# OutputIndicator_v1p2.net
KiCad netlist of a schematic drawn in EAGLE
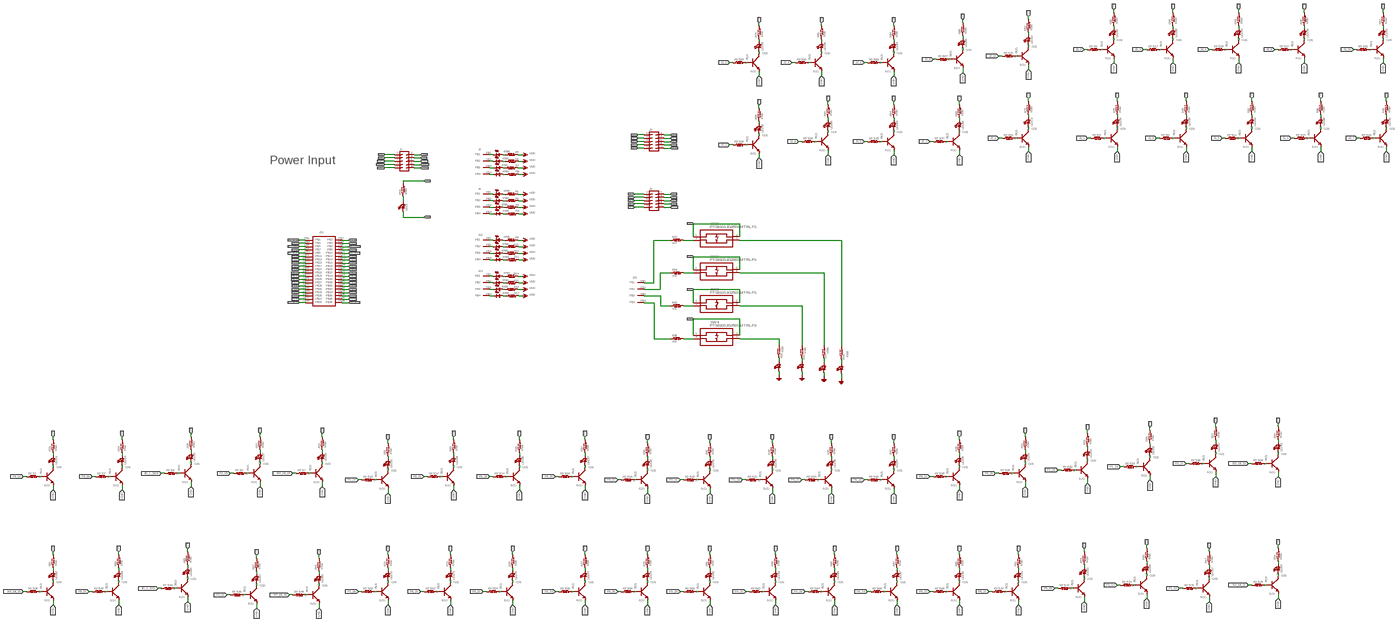
[diagram p0: schematic, sheet 1, overview]
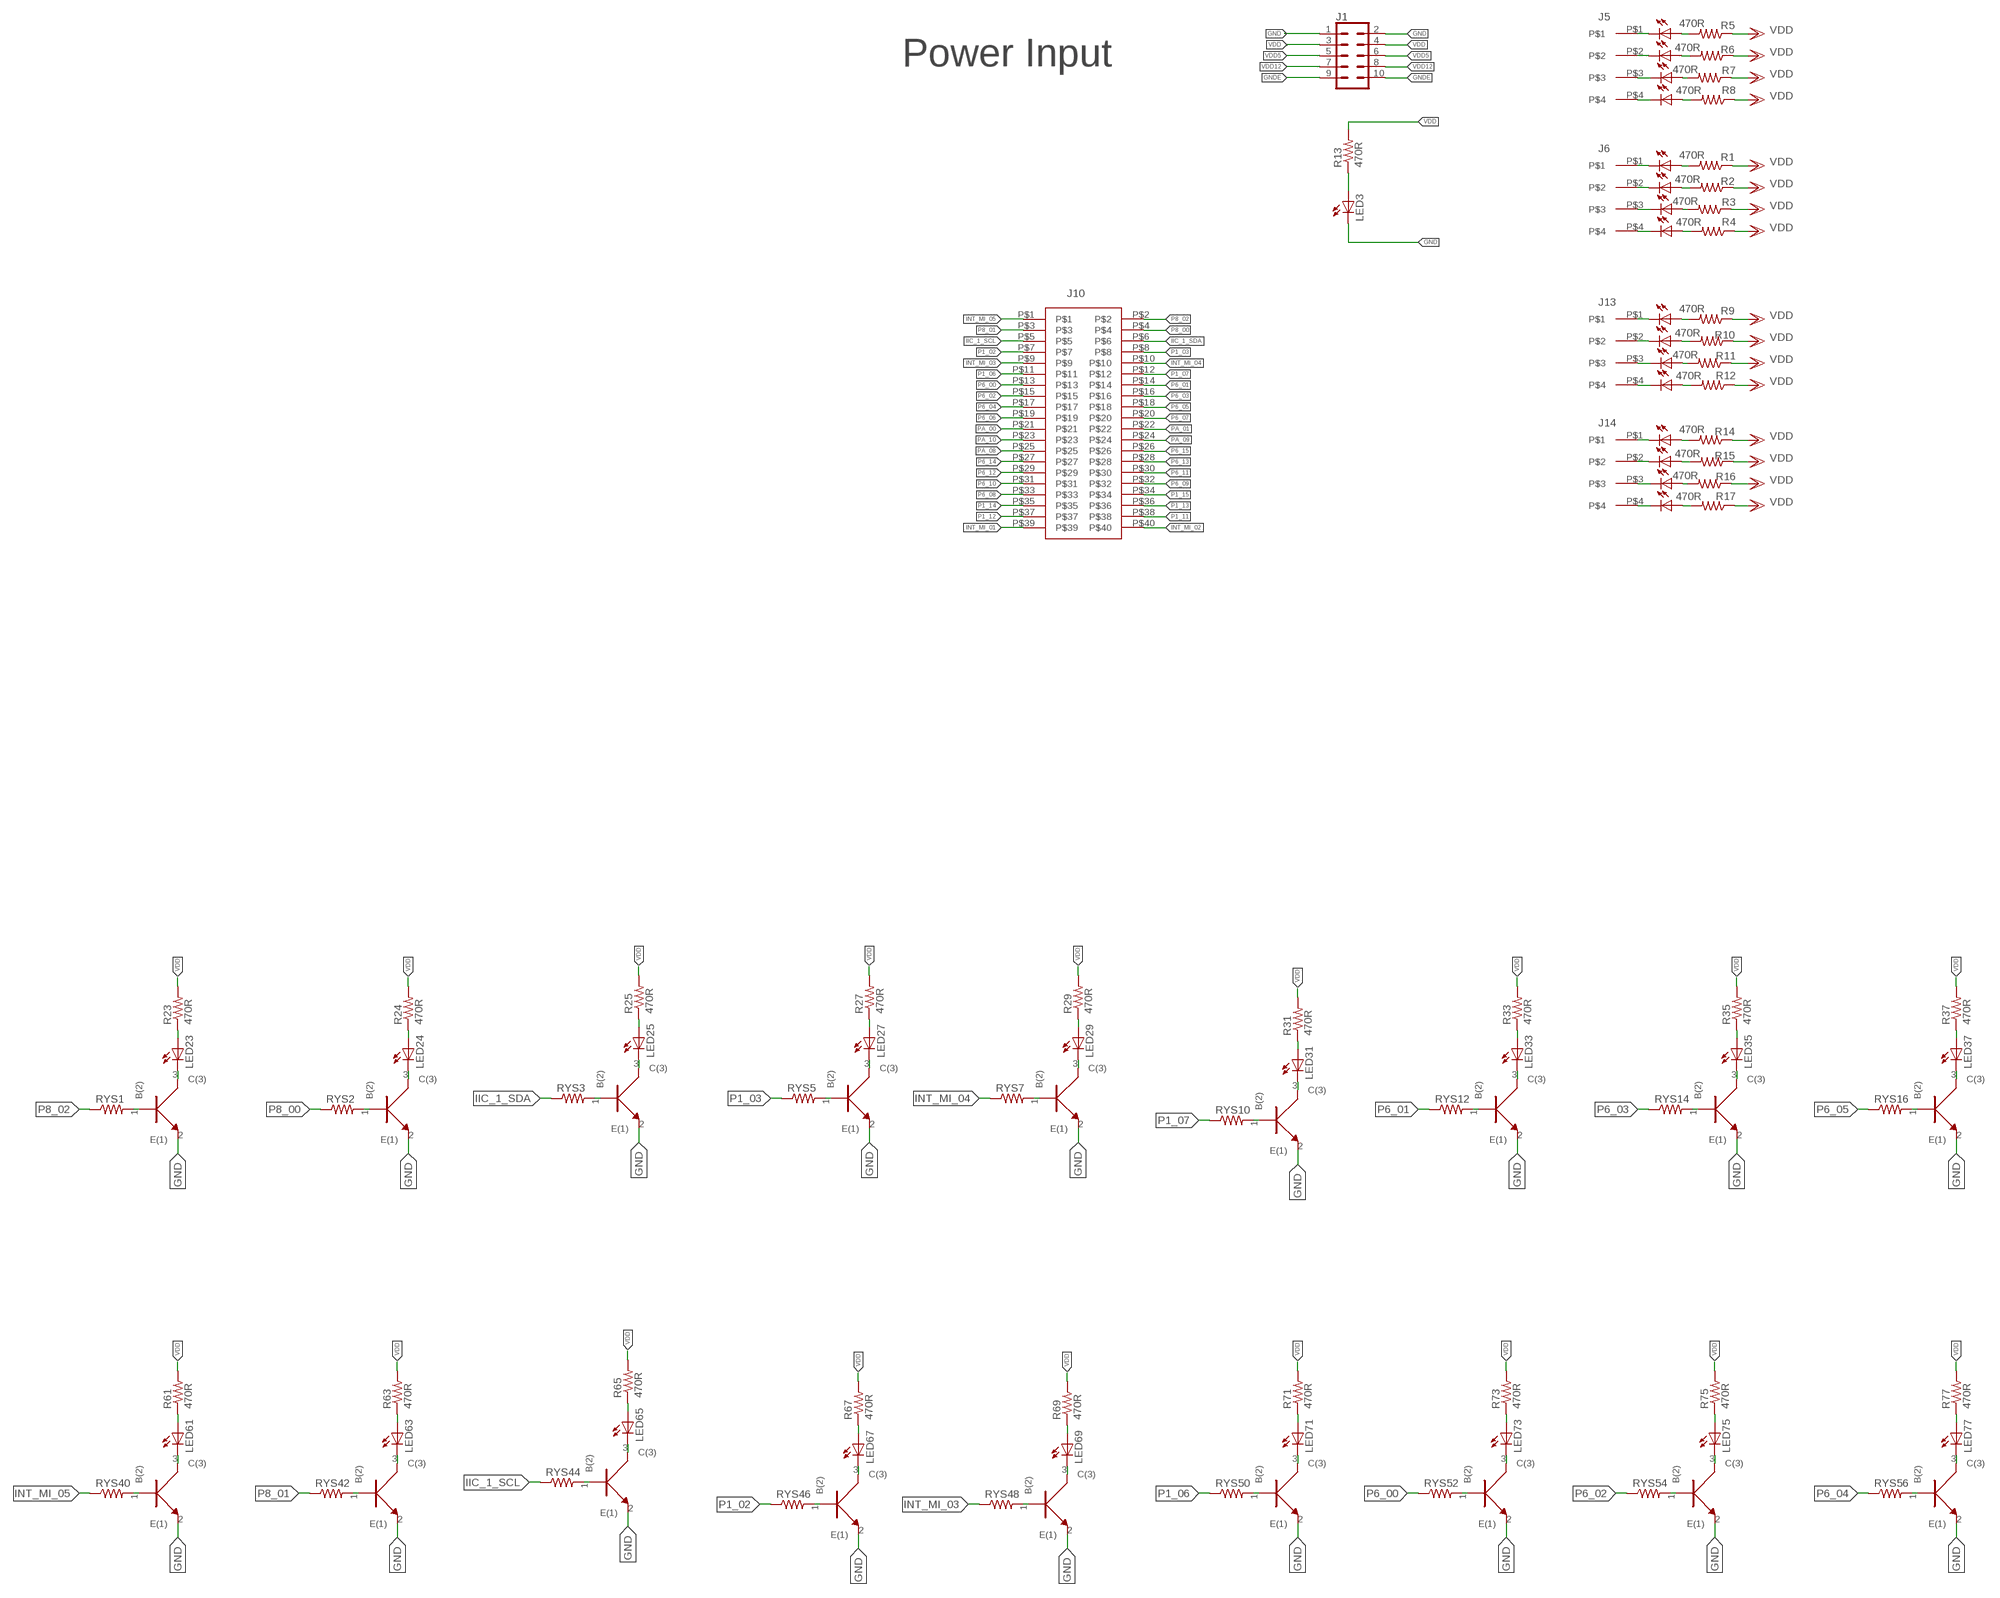
[diagram p1: schematic, sheet 1, part 1 of 5]
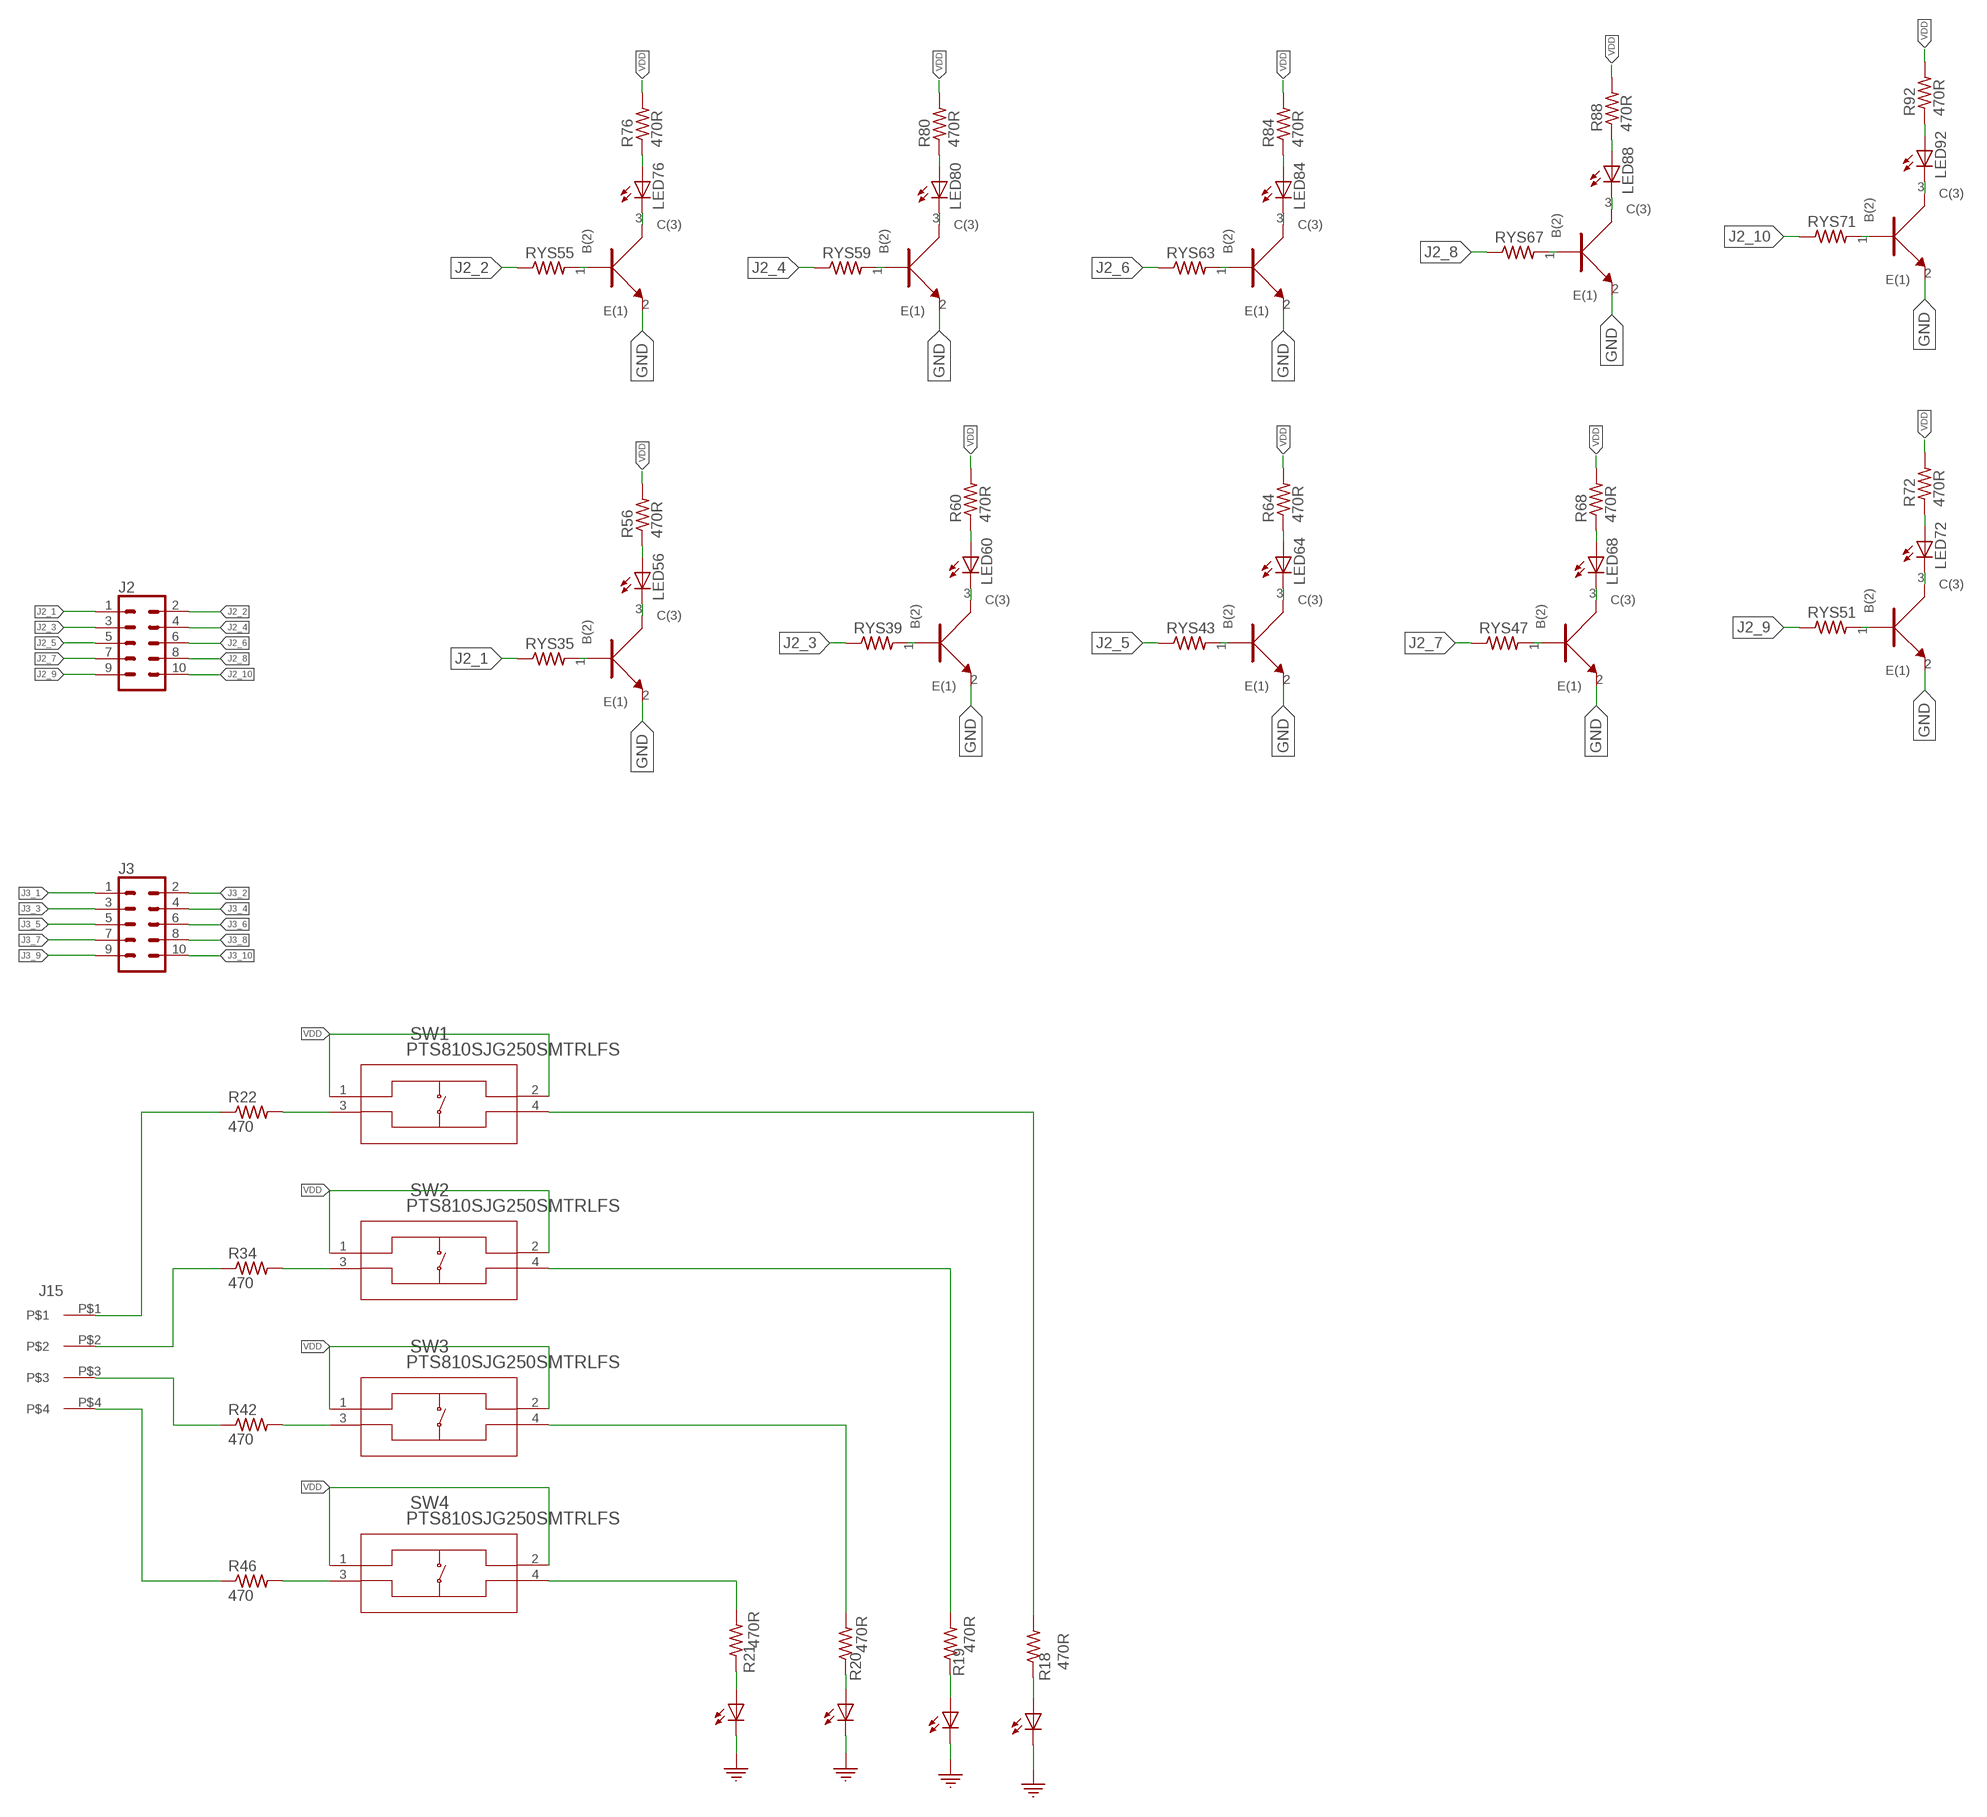
[diagram p2: schematic, sheet 1, part 2 of 5]
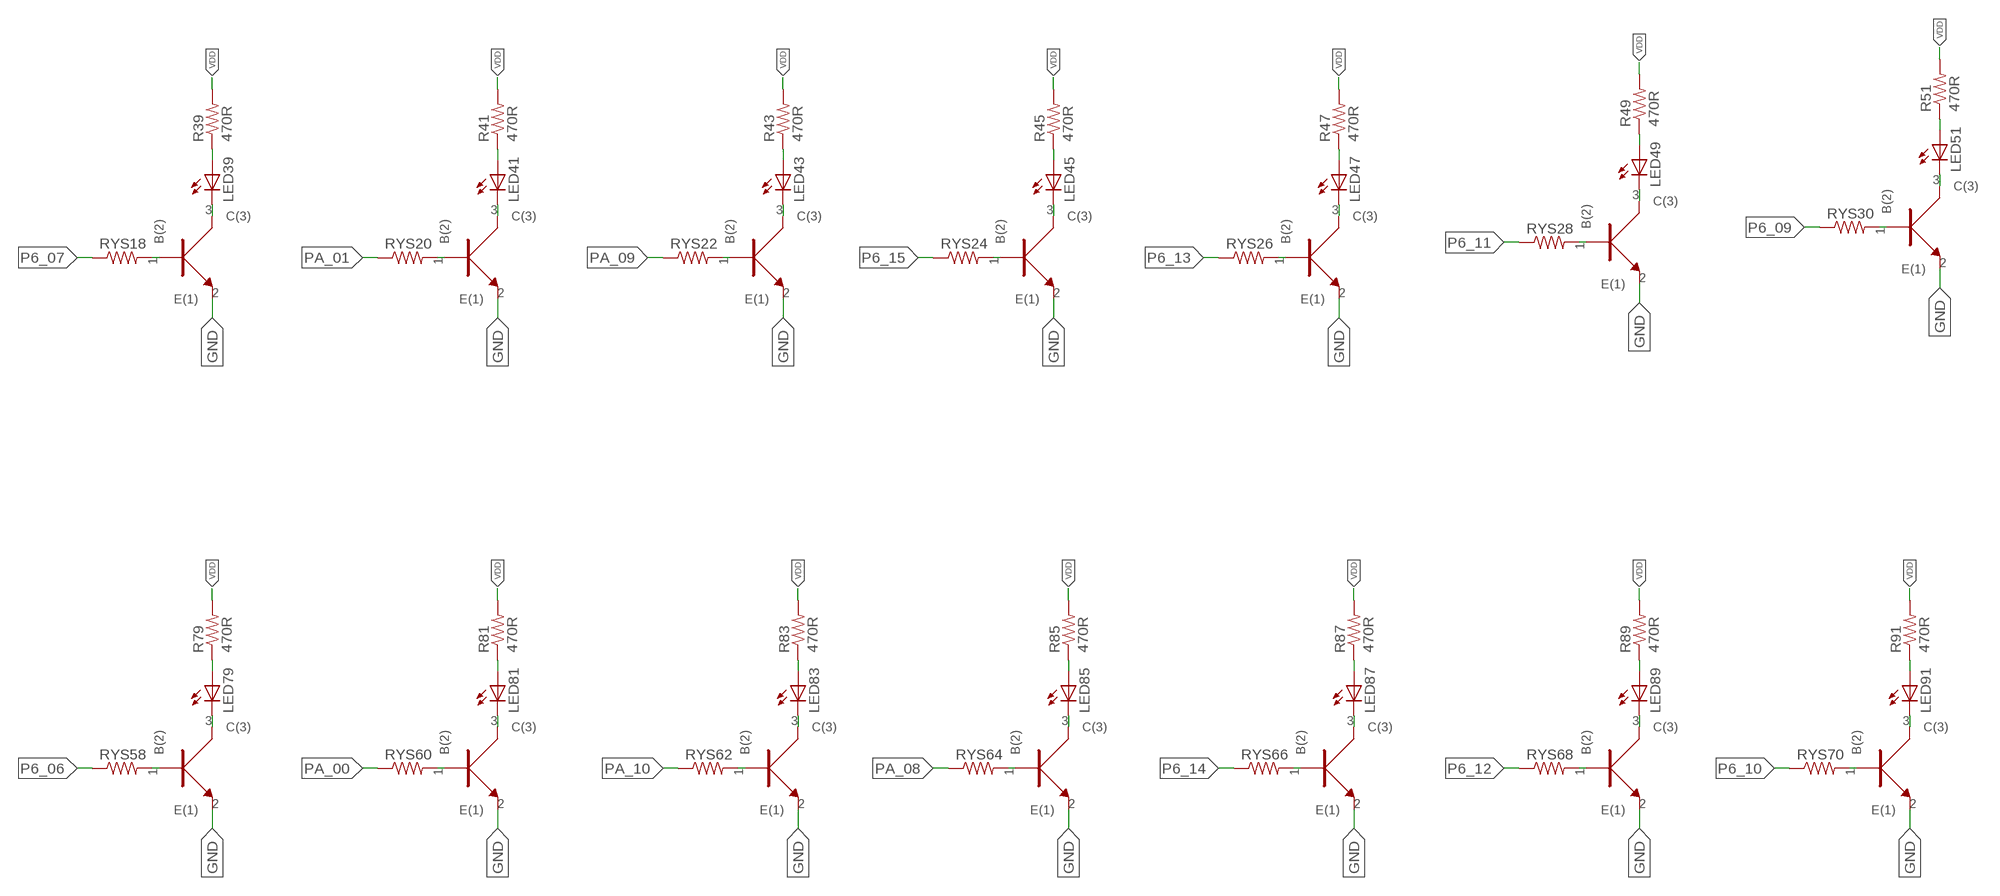
[diagram p3: schematic, sheet 1, part 3 of 5]
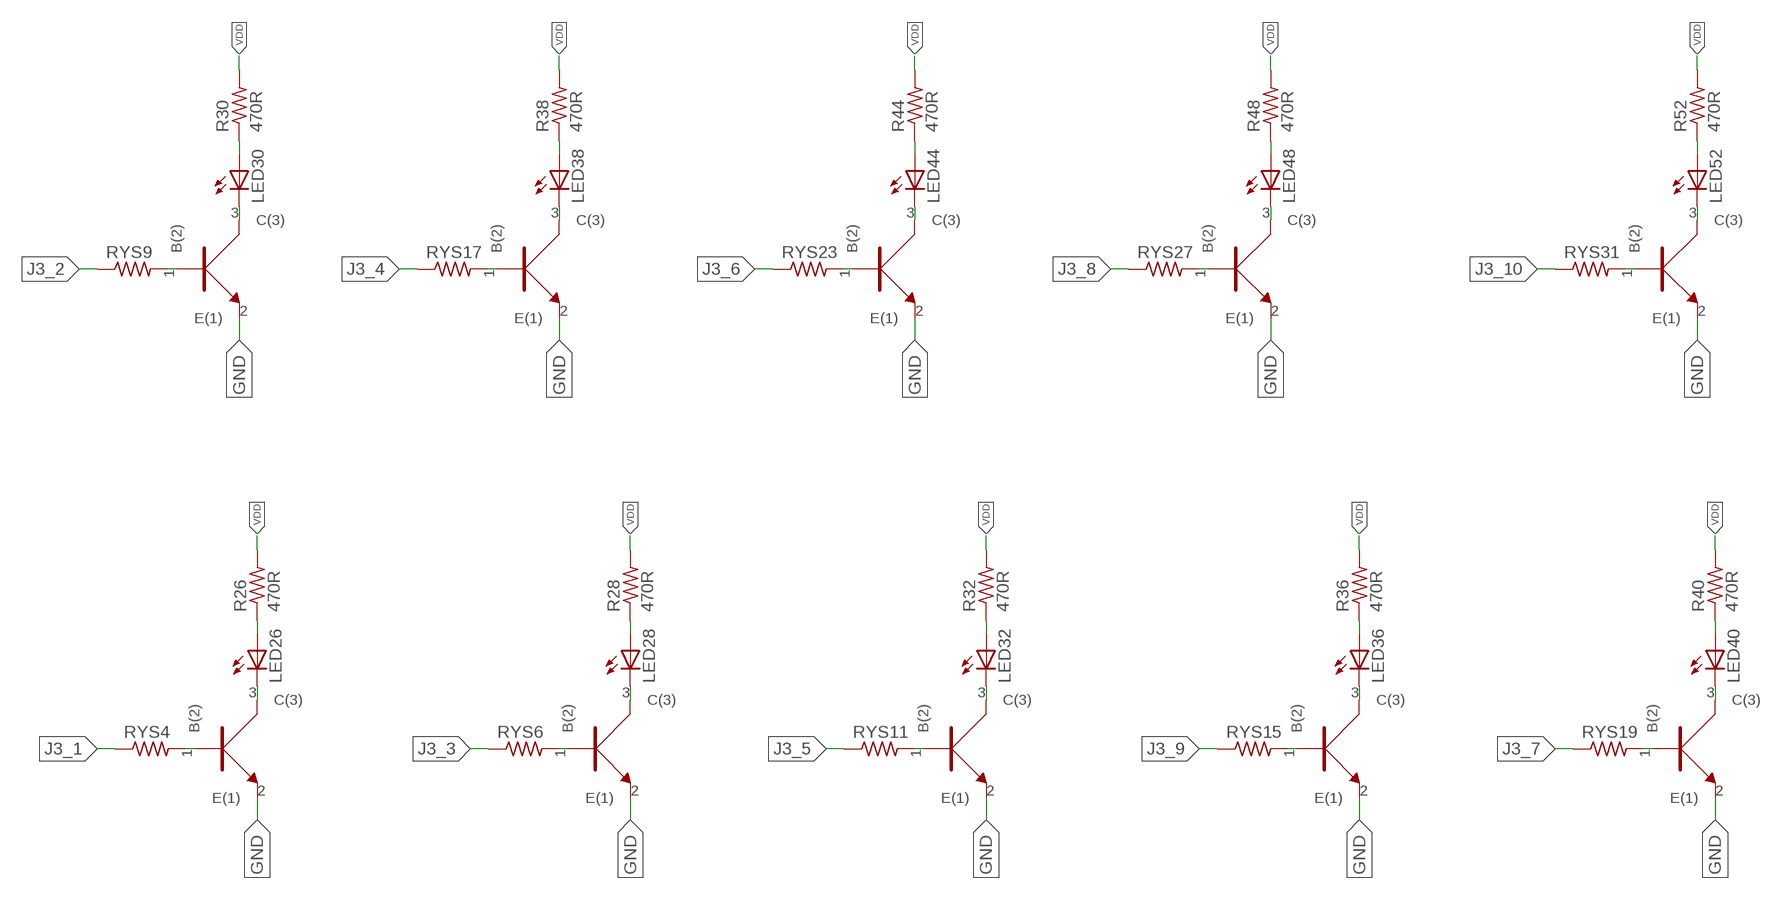
[diagram p4: schematic, sheet 1, part 4 of 5]
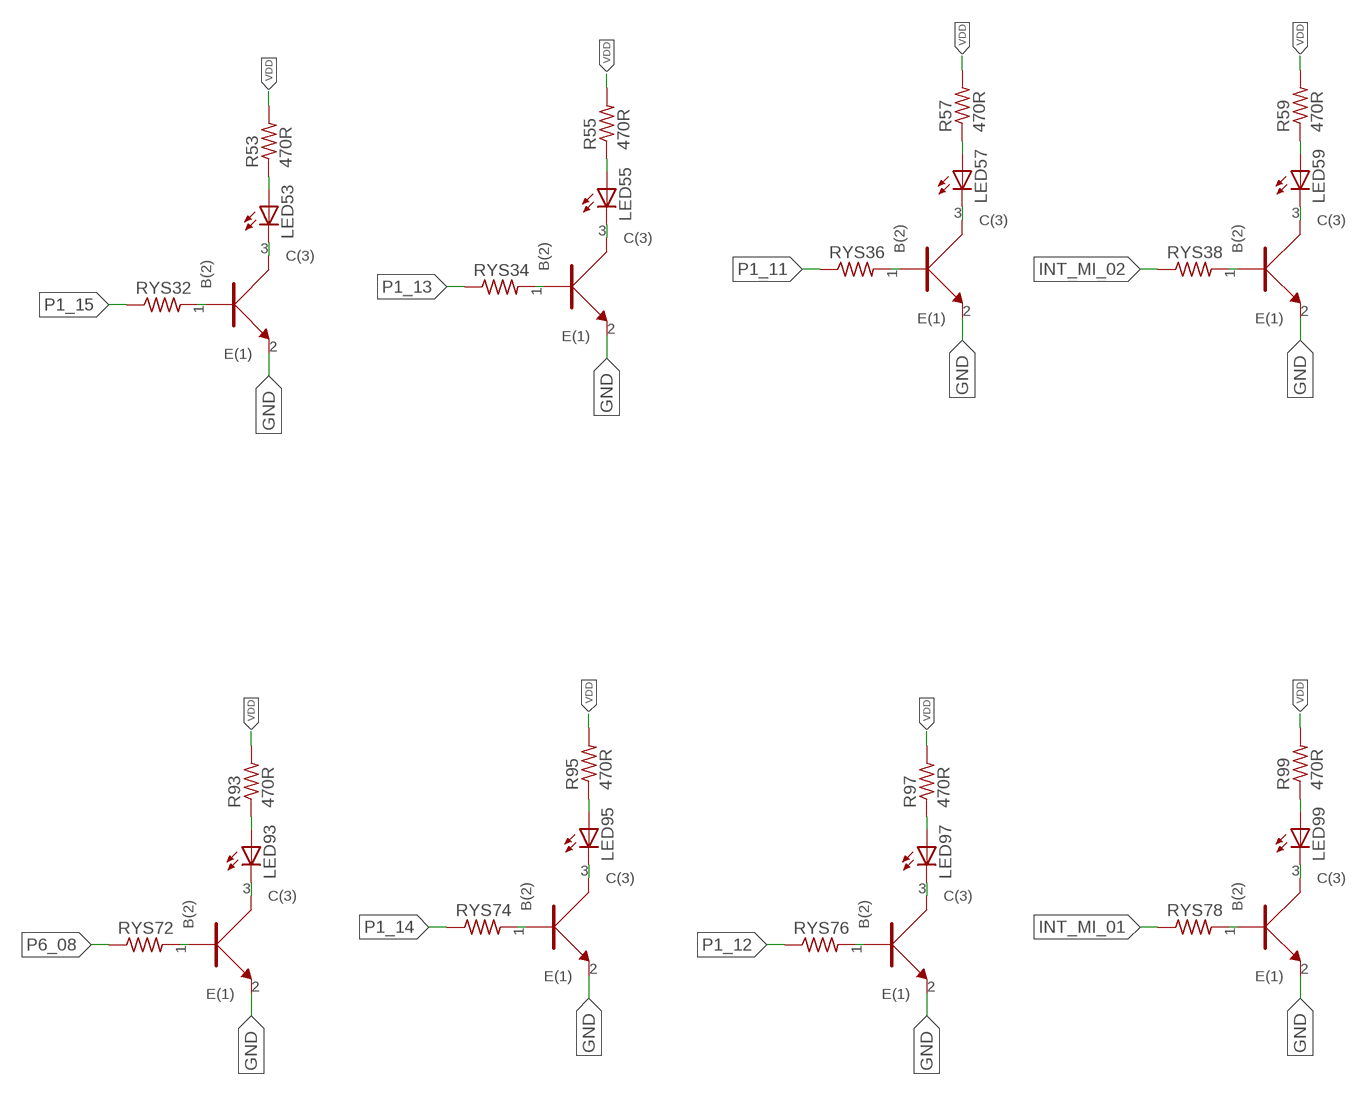
[diagram p5: schematic, sheet 1, part 5 of 5]

(export (version "E")
  (design (tool "Eeschema 10.0.6"))
  (components
    (comp (ref "J1")
      (value "CONN_05X2PTH")
      (footprint "eagle-import:2X5")
      (libsource (lib "eagle-import") (part "CONN_05X2PTH"))
    )
    (comp (ref "J2")
      (value "CONN_05X2PTH")
      (footprint "eagle-import:2X5")
      (libsource (lib "eagle-import") (part "CONN_05X2PTH"))
    )
    (comp (ref "J3")
      (value "CONN_05X2PTH")
      (footprint "eagle-import:2X5")
      (libsource (lib "eagle-import") (part "CONN_05X2PTH"))
    )
    (comp (ref "J5")
      (value "3.81MM_1_X_4_RT_ANGLE_PLUG_HEADER")
      (footprint "eagle-import:1X4_3.81MM_PITCH")
      (libsource (lib "eagle-import") (part "3.81MM_1_X_4_RT_ANGLE_PLUG_HEADER"))
    )
    (comp (ref "J6")
      (value "3.81MM_1_X_4_RT_ANGLE_PLUG_HEADER")
      (footprint "eagle-import:1X4_3.81MM_PITCH")
      (libsource (lib "eagle-import") (part "3.81MM_1_X_4_RT_ANGLE_PLUG_HEADER"))
    )
    (comp (ref "J10")
      (value "HEADER_2_X_20_GENERIC")
      (footprint "eagle-import:HEADER_2_X_20_.1_INCH")
      (libsource (lib "eagle-import") (part "HEADER_2_X_20_GENERIC"))
    )
    (comp (ref "J13")
      (value "3.81MM_1_X_4_RT_ANGLE_PLUG_HEADER")
      (footprint "eagle-import:1X4_3.81MM_PITCH")
      (libsource (lib "eagle-import") (part "3.81MM_1_X_4_RT_ANGLE_PLUG_HEADER"))
    )
    (comp (ref "J14")
      (value "3.81MM_1_X_4_RT_ANGLE_PLUG_HEADER")
      (footprint "eagle-import:1X4_3.81MM_PITCH")
      (libsource (lib "eagle-import") (part "3.81MM_1_X_4_RT_ANGLE_PLUG_HEADER"))
    )
    (comp (ref "J15")
      (value "3.81MM_1_X_4_RT_ANGLE_PLUG_HEADER")
      (footprint "eagle-import:1X4_3.81MM_PITCH")
      (libsource (lib "eagle-import") (part "3.81MM_1_X_4_RT_ANGLE_PLUG_HEADER"))
    )
    (comp (ref "LED1")
      (value "LED_0805_GREEN")
      (footprint "eagle-import:LED_0805_GREEN")
      (libsource (lib "eagle-import") (part "LED_0805_GREEN"))
    )
    (comp (ref "LED2")
      (value "LED_0805_GREEN")
      (footprint "eagle-import:LED_0805_GREEN")
      (libsource (lib "eagle-import") (part "LED_0805_GREEN"))
    )
    (comp (ref "LED3")
      (value "LED_0805_GREEN")
      (footprint "eagle-import:LED_0805_GREEN")
      (libsource (lib "eagle-import") (part "LED_0805_GREEN"))
    )
    (comp (ref "LED4")
      (value "LED_0805_GREEN")
      (footprint "eagle-import:LED_0805_GREEN")
      (libsource (lib "eagle-import") (part "LED_0805_GREEN"))
    )
    (comp (ref "LED5")
      (value "LED_0805_GREEN")
      (footprint "eagle-import:LED_0805_GREEN")
      (libsource (lib "eagle-import") (part "LED_0805_GREEN"))
    )
    (comp (ref "LED6")
      (value "LED_0805_GREEN")
      (footprint "eagle-import:LED_0805_GREEN")
      (libsource (lib "eagle-import") (part "LED_0805_GREEN"))
    )
    (comp (ref "LED7")
      (value "LED_0805_GREEN")
      (footprint "eagle-import:LED_0805_GREEN")
      (libsource (lib "eagle-import") (part "LED_0805_GREEN"))
    )
    (comp (ref "LED8")
      (value "LED_0805_GREEN")
      (footprint "eagle-import:LED_0805_GREEN")
      (libsource (lib "eagle-import") (part "LED_0805_GREEN"))
    )
    (comp (ref "LED9")
      (value "LED_0805_GREEN")
      (footprint "eagle-import:LED_0805_GREEN")
      (libsource (lib "eagle-import") (part "LED_0805_GREEN"))
    )
    (comp (ref "LED10")
      (value "LED_0805_GREEN")
      (footprint "eagle-import:LED_0805_GREEN")
      (libsource (lib "eagle-import") (part "LED_0805_GREEN"))
    )
    (comp (ref "LED11")
      (value "LED_0805_GREEN")
      (footprint "eagle-import:LED_0805_GREEN")
      (libsource (lib "eagle-import") (part "LED_0805_GREEN"))
    )
    (comp (ref "LED12")
      (value "LED_0805_GREEN")
      (footprint "eagle-import:LED_0805_GREEN")
      (libsource (lib "eagle-import") (part "LED_0805_GREEN"))
    )
    (comp (ref "LED13")
      (value "LED_0805_GREEN")
      (footprint "eagle-import:LED_0805_GREEN")
      (libsource (lib "eagle-import") (part "LED_0805_GREEN"))
    )
    (comp (ref "LED14")
      (value "LED_0805_GREEN")
      (footprint "eagle-import:LED_0805_GREEN")
      (libsource (lib "eagle-import") (part "LED_0805_GREEN"))
    )
    (comp (ref "LED15")
      (value "LED_0805_GREEN")
      (footprint "eagle-import:LED_0805_GREEN")
      (libsource (lib "eagle-import") (part "LED_0805_GREEN"))
    )
    (comp (ref "LED16")
      (value "LED_0805_GREEN")
      (footprint "eagle-import:LED_0805_GREEN")
      (libsource (lib "eagle-import") (part "LED_0805_GREEN"))
    )
    (comp (ref "LED17")
      (value "LED_0805_GREEN")
      (footprint "eagle-import:LED_0805_GREEN")
      (libsource (lib "eagle-import") (part "LED_0805_GREEN"))
    )
    (comp (ref "LED18")
      (value "LED_0805_GREEN")
      (footprint "eagle-import:LED_0805_GREEN")
      (libsource (lib "eagle-import") (part "LED_0805_GREEN"))
    )
    (comp (ref "LED19")
      (value "LED_0805_GREEN")
      (footprint "eagle-import:LED_0805_GREEN")
      (libsource (lib "eagle-import") (part "LED_0805_GREEN"))
    )
    (comp (ref "LED20")
      (value "LED_0805_GREEN")
      (footprint "eagle-import:LED_0805_GREEN")
      (libsource (lib "eagle-import") (part "LED_0805_GREEN"))
    )
    (comp (ref "LED21")
      (value "LED_0805_GREEN")
      (footprint "eagle-import:LED_0805_GREEN")
      (libsource (lib "eagle-import") (part "LED_0805_GREEN"))
    )
    (comp (ref "LED23")
      (value "LED_0805_GREEN")
      (footprint "eagle-import:LED_0805_GREEN")
      (libsource (lib "eagle-import") (part "LED_0805_GREEN"))
    )
    (comp (ref "LED24")
      (value "LED_0805_GREEN")
      (footprint "eagle-import:LED_0805_GREEN")
      (libsource (lib "eagle-import") (part "LED_0805_GREEN"))
    )
    (comp (ref "LED25")
      (value "LED_0805_GREEN")
      (footprint "eagle-import:LED_0805_GREEN")
      (libsource (lib "eagle-import") (part "LED_0805_GREEN"))
    )
    (comp (ref "LED26")
      (value "LED_0805_GREEN")
      (footprint "eagle-import:LED_0805_GREEN")
      (libsource (lib "eagle-import") (part "LED_0805_GREEN"))
    )
    (comp (ref "LED27")
      (value "LED_0805_GREEN")
      (footprint "eagle-import:LED_0805_GREEN")
      (libsource (lib "eagle-import") (part "LED_0805_GREEN"))
    )
    (comp (ref "LED28")
      (value "LED_0805_GREEN")
      (footprint "eagle-import:LED_0805_GREEN")
      (libsource (lib "eagle-import") (part "LED_0805_GREEN"))
    )
    (comp (ref "LED29")
      (value "LED_0805_GREEN")
      (footprint "eagle-import:LED_0805_GREEN")
      (libsource (lib "eagle-import") (part "LED_0805_GREEN"))
    )
    (comp (ref "LED30")
      (value "LED_0805_GREEN")
      (footprint "eagle-import:LED_0805_GREEN")
      (libsource (lib "eagle-import") (part "LED_0805_GREEN"))
    )
    (comp (ref "LED31")
      (value "LED_0805_GREEN")
      (footprint "eagle-import:LED_0805_GREEN")
      (libsource (lib "eagle-import") (part "LED_0805_GREEN"))
    )
    (comp (ref "LED32")
      (value "LED_0805_GREEN")
      (footprint "eagle-import:LED_0805_GREEN")
      (libsource (lib "eagle-import") (part "LED_0805_GREEN"))
    )
    (comp (ref "LED33")
      (value "LED_0805_GREEN")
      (footprint "eagle-import:LED_0805_GREEN")
      (libsource (lib "eagle-import") (part "LED_0805_GREEN"))
    )
    (comp (ref "LED35")
      (value "LED_0805_GREEN")
      (footprint "eagle-import:LED_0805_GREEN")
      (libsource (lib "eagle-import") (part "LED_0805_GREEN"))
    )
    (comp (ref "LED36")
      (value "LED_0805_GREEN")
      (footprint "eagle-import:LED_0805_GREEN")
      (libsource (lib "eagle-import") (part "LED_0805_GREEN"))
    )
    (comp (ref "LED37")
      (value "LED_0805_GREEN")
      (footprint "eagle-import:LED_0805_GREEN")
      (libsource (lib "eagle-import") (part "LED_0805_GREEN"))
    )
    (comp (ref "LED38")
      (value "LED_0805_GREEN")
      (footprint "eagle-import:LED_0805_GREEN")
      (libsource (lib "eagle-import") (part "LED_0805_GREEN"))
    )
    (comp (ref "LED39")
      (value "LED_0805_GREEN")
      (footprint "eagle-import:LED_0805_GREEN")
      (libsource (lib "eagle-import") (part "LED_0805_GREEN"))
    )
    (comp (ref "LED40")
      (value "LED_0805_GREEN")
      (footprint "eagle-import:LED_0805_GREEN")
      (libsource (lib "eagle-import") (part "LED_0805_GREEN"))
    )
    (comp (ref "LED41")
      (value "LED_0805_GREEN")
      (footprint "eagle-import:LED_0805_GREEN")
      (libsource (lib "eagle-import") (part "LED_0805_GREEN"))
    )
    (comp (ref "LED43")
      (value "LED_0805_GREEN")
      (footprint "eagle-import:LED_0805_GREEN")
      (libsource (lib "eagle-import") (part "LED_0805_GREEN"))
    )
    (comp (ref "LED44")
      (value "LED_0805_GREEN")
      (footprint "eagle-import:LED_0805_GREEN")
      (libsource (lib "eagle-import") (part "LED_0805_GREEN"))
    )
    (comp (ref "LED45")
      (value "LED_0805_GREEN")
      (footprint "eagle-import:LED_0805_GREEN")
      (libsource (lib "eagle-import") (part "LED_0805_GREEN"))
    )
    (comp (ref "LED47")
      (value "LED_0805_GREEN")
      (footprint "eagle-import:LED_0805_GREEN")
      (libsource (lib "eagle-import") (part "LED_0805_GREEN"))
    )
    (comp (ref "LED48")
      (value "LED_0805_GREEN")
      (footprint "eagle-import:LED_0805_GREEN")
      (libsource (lib "eagle-import") (part "LED_0805_GREEN"))
    )
    (comp (ref "LED49")
      (value "LED_0805_GREEN")
      (footprint "eagle-import:LED_0805_GREEN")
      (libsource (lib "eagle-import") (part "LED_0805_GREEN"))
    )
    (comp (ref "LED51")
      (value "LED_0805_GREEN")
      (footprint "eagle-import:LED_0805_GREEN")
      (libsource (lib "eagle-import") (part "LED_0805_GREEN"))
    )
    (comp (ref "LED52")
      (value "LED_0805_GREEN")
      (footprint "eagle-import:LED_0805_GREEN")
      (libsource (lib "eagle-import") (part "LED_0805_GREEN"))
    )
    (comp (ref "LED53")
      (value "LED_0805_GREEN")
      (footprint "eagle-import:LED_0805_GREEN")
      (libsource (lib "eagle-import") (part "LED_0805_GREEN"))
    )
    (comp (ref "LED55")
      (value "LED_0805_GREEN")
      (footprint "eagle-import:LED_0805_GREEN")
      (libsource (lib "eagle-import") (part "LED_0805_GREEN"))
    )
    (comp (ref "LED56")
      (value "LED_0805_GREEN")
      (footprint "eagle-import:LED_0805_GREEN")
      (libsource (lib "eagle-import") (part "LED_0805_GREEN"))
    )
    (comp (ref "LED57")
      (value "LED_0805_GREEN")
      (footprint "eagle-import:LED_0805_GREEN")
      (libsource (lib "eagle-import") (part "LED_0805_GREEN"))
    )
    (comp (ref "LED59")
      (value "LED_0805_GREEN")
      (footprint "eagle-import:LED_0805_GREEN")
      (libsource (lib "eagle-import") (part "LED_0805_GREEN"))
    )
    (comp (ref "LED60")
      (value "LED_0805_GREEN")
      (footprint "eagle-import:LED_0805_GREEN")
      (libsource (lib "eagle-import") (part "LED_0805_GREEN"))
    )
    (comp (ref "LED61")
      (value "LED_0805_GREEN")
      (footprint "eagle-import:LED_0805_GREEN")
      (libsource (lib "eagle-import") (part "LED_0805_GREEN"))
    )
    (comp (ref "LED63")
      (value "LED_0805_GREEN")
      (footprint "eagle-import:LED_0805_GREEN")
      (libsource (lib "eagle-import") (part "LED_0805_GREEN"))
    )
    (comp (ref "LED64")
      (value "LED_0805_GREEN")
      (footprint "eagle-import:LED_0805_GREEN")
      (libsource (lib "eagle-import") (part "LED_0805_GREEN"))
    )
    (comp (ref "LED65")
      (value "LED_0805_GREEN")
      (footprint "eagle-import:LED_0805_GREEN")
      (libsource (lib "eagle-import") (part "LED_0805_GREEN"))
    )
    (comp (ref "LED67")
      (value "LED_0805_GREEN")
      (footprint "eagle-import:LED_0805_GREEN")
      (libsource (lib "eagle-import") (part "LED_0805_GREEN"))
    )
    (comp (ref "LED68")
      (value "LED_0805_GREEN")
      (footprint "eagle-import:LED_0805_GREEN")
      (libsource (lib "eagle-import") (part "LED_0805_GREEN"))
    )
    (comp (ref "LED69")
      (value "LED_0805_GREEN")
      (footprint "eagle-import:LED_0805_GREEN")
      (libsource (lib "eagle-import") (part "LED_0805_GREEN"))
    )
    (comp (ref "LED71")
      (value "LED_0805_GREEN")
      (footprint "eagle-import:LED_0805_GREEN")
      (libsource (lib "eagle-import") (part "LED_0805_GREEN"))
    )
    (comp (ref "LED72")
      (value "LED_0805_GREEN")
      (footprint "eagle-import:LED_0805_GREEN")
      (libsource (lib "eagle-import") (part "LED_0805_GREEN"))
    )
    (comp (ref "LED73")
      (value "LED_0805_GREEN")
      (footprint "eagle-import:LED_0805_GREEN")
      (libsource (lib "eagle-import") (part "LED_0805_GREEN"))
    )
    (comp (ref "LED75")
      (value "LED_0805_GREEN")
      (footprint "eagle-import:LED_0805_GREEN")
      (libsource (lib "eagle-import") (part "LED_0805_GREEN"))
    )
    (comp (ref "LED76")
      (value "LED_0805_GREEN")
      (footprint "eagle-import:LED_0805_GREEN")
      (libsource (lib "eagle-import") (part "LED_0805_GREEN"))
    )
    (comp (ref "LED77")
      (value "LED_0805_GREEN")
      (footprint "eagle-import:LED_0805_GREEN")
      (libsource (lib "eagle-import") (part "LED_0805_GREEN"))
    )
    (comp (ref "LED79")
      (value "LED_0805_GREEN")
      (footprint "eagle-import:LED_0805_GREEN")
      (libsource (lib "eagle-import") (part "LED_0805_GREEN"))
    )
    (comp (ref "LED80")
      (value "LED_0805_GREEN")
      (footprint "eagle-import:LED_0805_GREEN")
      (libsource (lib "eagle-import") (part "LED_0805_GREEN"))
    )
    (comp (ref "LED81")
      (value "LED_0805_GREEN")
      (footprint "eagle-import:LED_0805_GREEN")
      (libsource (lib "eagle-import") (part "LED_0805_GREEN"))
    )
    (comp (ref "LED83")
      (value "LED_0805_GREEN")
      (footprint "eagle-import:LED_0805_GREEN")
      (libsource (lib "eagle-import") (part "LED_0805_GREEN"))
    )
    (comp (ref "LED84")
      (value "LED_0805_GREEN")
      (footprint "eagle-import:LED_0805_GREEN")
      (libsource (lib "eagle-import") (part "LED_0805_GREEN"))
    )
    (comp (ref "LED85")
      (value "LED_0805_GREEN")
      (footprint "eagle-import:LED_0805_GREEN")
      (libsource (lib "eagle-import") (part "LED_0805_GREEN"))
    )
    (comp (ref "LED87")
      (value "LED_0805_GREEN")
      (footprint "eagle-import:LED_0805_GREEN")
      (libsource (lib "eagle-import") (part "LED_0805_GREEN"))
    )
    (comp (ref "LED88")
      (value "LED_0805_GREEN")
      (footprint "eagle-import:LED_0805_GREEN")
      (libsource (lib "eagle-import") (part "LED_0805_GREEN"))
    )
    (comp (ref "LED89")
      (value "LED_0805_GREEN")
      (footprint "eagle-import:LED_0805_GREEN")
      (libsource (lib "eagle-import") (part "LED_0805_GREEN"))
    )
    (comp (ref "LED91")
      (value "LED_0805_GREEN")
      (footprint "eagle-import:LED_0805_GREEN")
      (libsource (lib "eagle-import") (part "LED_0805_GREEN"))
    )
    (comp (ref "LED92")
      (value "LED_0805_GREEN")
      (footprint "eagle-import:LED_0805_GREEN")
      (libsource (lib "eagle-import") (part "LED_0805_GREEN"))
    )
    (comp (ref "LED93")
      (value "LED_0805_GREEN")
      (footprint "eagle-import:LED_0805_GREEN")
      (libsource (lib "eagle-import") (part "LED_0805_GREEN"))
    )
    (comp (ref "LED95")
      (value "LED_0805_GREEN")
      (footprint "eagle-import:LED_0805_GREEN")
      (libsource (lib "eagle-import") (part "LED_0805_GREEN"))
    )
    (comp (ref "LED97")
      (value "LED_0805_GREEN")
      (footprint "eagle-import:LED_0805_GREEN")
      (libsource (lib "eagle-import") (part "LED_0805_GREEN"))
    )
    (comp (ref "LED99")
      (value "LED_0805_GREEN")
      (footprint "eagle-import:LED_0805_GREEN")
      (libsource (lib "eagle-import") (part "LED_0805_GREEN"))
    )
    (comp (ref "R1")
      (value "470R")
      (footprint "eagle-import:0402")
      (libsource (lib "eagle-import") (part "R_0402"))
    )
    (comp (ref "R2")
      (value "470R")
      (footprint "eagle-import:0402")
      (libsource (lib "eagle-import") (part "R_0402"))
    )
    (comp (ref "R3")
      (value "470R")
      (footprint "eagle-import:0402")
      (libsource (lib "eagle-import") (part "R_0402"))
    )
    (comp (ref "R4")
      (value "470R")
      (footprint "eagle-import:0402")
      (libsource (lib "eagle-import") (part "R_0402"))
    )
    (comp (ref "R5")
      (value "470R")
      (footprint "eagle-import:0402")
      (libsource (lib "eagle-import") (part "R_0402"))
    )
    (comp (ref "R6")
      (value "470R")
      (footprint "eagle-import:0402")
      (libsource (lib "eagle-import") (part "R_0402"))
    )
    (comp (ref "R7")
      (value "470R")
      (footprint "eagle-import:0402")
      (libsource (lib "eagle-import") (part "R_0402"))
    )
    (comp (ref "R8")
      (value "470R")
      (footprint "eagle-import:0402")
      (libsource (lib "eagle-import") (part "R_0402"))
    )
    (comp (ref "R9")
      (value "470R")
      (footprint "eagle-import:0402")
      (libsource (lib "eagle-import") (part "R_0402"))
    )
    (comp (ref "R10")
      (value "470R")
      (footprint "eagle-import:0402")
      (libsource (lib "eagle-import") (part "R_0402"))
    )
    (comp (ref "R11")
      (value "470R")
      (footprint "eagle-import:0402")
      (libsource (lib "eagle-import") (part "R_0402"))
    )
    (comp (ref "R12")
      (value "470R")
      (footprint "eagle-import:0402")
      (libsource (lib "eagle-import") (part "R_0402"))
    )
    (comp (ref "R13")
      (value "470R")
      (footprint "eagle-import:0402")
      (libsource (lib "eagle-import") (part "R_0402"))
    )
    (comp (ref "R14")
      (value "470R")
      (footprint "eagle-import:0402")
      (libsource (lib "eagle-import") (part "R_0402"))
    )
    (comp (ref "R15")
      (value "470R")
      (footprint "eagle-import:0402")
      (libsource (lib "eagle-import") (part "R_0402"))
    )
    (comp (ref "R16")
      (value "470R")
      (footprint "eagle-import:0402")
      (libsource (lib "eagle-import") (part "R_0402"))
    )
    (comp (ref "R17")
      (value "470R")
      (footprint "eagle-import:0402")
      (libsource (lib "eagle-import") (part "R_0402"))
    )
    (comp (ref "R18")
      (value "470R")
      (footprint "eagle-import:0402")
      (libsource (lib "eagle-import") (part "R_0402"))
    )
    (comp (ref "R19")
      (value "470R")
      (footprint "eagle-import:0402")
      (libsource (lib "eagle-import") (part "R_0402"))
    )
    (comp (ref "R20")
      (value "470R")
      (footprint "eagle-import:0402")
      (libsource (lib "eagle-import") (part "R_0402"))
    )
    (comp (ref "R21")
      (value "470R")
      (footprint "eagle-import:0402")
      (libsource (lib "eagle-import") (part "R_0402"))
    )
    (comp (ref "R22")
      (value "470")
      (footprint "eagle-import:0402")
      (libsource (lib "eagle-import") (part "R_0402"))
    )
    (comp (ref "R23")
      (value "470R")
      (footprint "eagle-import:0402")
      (libsource (lib "eagle-import") (part "R_0402"))
    )
    (comp (ref "R24")
      (value "470R")
      (footprint "eagle-import:0402")
      (libsource (lib "eagle-import") (part "R_0402"))
    )
    (comp (ref "R25")
      (value "470R")
      (footprint "eagle-import:0402")
      (libsource (lib "eagle-import") (part "R_0402"))
    )
    (comp (ref "R26")
      (value "470R")
      (footprint "eagle-import:0402")
      (libsource (lib "eagle-import") (part "R_0402"))
    )
    (comp (ref "R27")
      (value "470R")
      (footprint "eagle-import:0402")
      (libsource (lib "eagle-import") (part "R_0402"))
    )
    (comp (ref "R28")
      (value "470R")
      (footprint "eagle-import:0402")
      (libsource (lib "eagle-import") (part "R_0402"))
    )
    (comp (ref "R29")
      (value "470R")
      (footprint "eagle-import:0402")
      (libsource (lib "eagle-import") (part "R_0402"))
    )
    (comp (ref "R30")
      (value "470R")
      (footprint "eagle-import:0402")
      (libsource (lib "eagle-import") (part "R_0402"))
    )
    (comp (ref "R31")
      (value "470R")
      (footprint "eagle-import:0402")
      (libsource (lib "eagle-import") (part "R_0402"))
    )
    (comp (ref "R32")
      (value "470R")
      (footprint "eagle-import:0402")
      (libsource (lib "eagle-import") (part "R_0402"))
    )
    (comp (ref "R33")
      (value "470R")
      (footprint "eagle-import:0402")
      (libsource (lib "eagle-import") (part "R_0402"))
    )
    (comp (ref "R34")
      (value "470")
      (footprint "eagle-import:0402")
      (libsource (lib "eagle-import") (part "R_0402"))
    )
    (comp (ref "R35")
      (value "470R")
      (footprint "eagle-import:0402")
      (libsource (lib "eagle-import") (part "R_0402"))
    )
    (comp (ref "R36")
      (value "470R")
      (footprint "eagle-import:0402")
      (libsource (lib "eagle-import") (part "R_0402"))
    )
    (comp (ref "R37")
      (value "470R")
      (footprint "eagle-import:0402")
      (libsource (lib "eagle-import") (part "R_0402"))
    )
    (comp (ref "R38")
      (value "470R")
      (footprint "eagle-import:0402")
      (libsource (lib "eagle-import") (part "R_0402"))
    )
    (comp (ref "R39")
      (value "470R")
      (footprint "eagle-import:0402")
      (libsource (lib "eagle-import") (part "R_0402"))
    )
    (comp (ref "R40")
      (value "470R")
      (footprint "eagle-import:0402")
      (libsource (lib "eagle-import") (part "R_0402"))
    )
    (comp (ref "R41")
      (value "470R")
      (footprint "eagle-import:0402")
      (libsource (lib "eagle-import") (part "R_0402"))
    )
    (comp (ref "R42")
      (value "470")
      (footprint "eagle-import:0402")
      (libsource (lib "eagle-import") (part "R_0402"))
    )
    (comp (ref "R43")
      (value "470R")
      (footprint "eagle-import:0402")
      (libsource (lib "eagle-import") (part "R_0402"))
    )
    (comp (ref "R44")
      (value "470R")
      (footprint "eagle-import:0402")
      (libsource (lib "eagle-import") (part "R_0402"))
    )
    (comp (ref "R45")
      (value "470R")
      (footprint "eagle-import:0402")
      (libsource (lib "eagle-import") (part "R_0402"))
    )
    (comp (ref "R46")
      (value "470")
      (footprint "eagle-import:0402")
      (libsource (lib "eagle-import") (part "R_0402"))
    )
    (comp (ref "R47")
      (value "470R")
      (footprint "eagle-import:0402")
      (libsource (lib "eagle-import") (part "R_0402"))
    )
    (comp (ref "R48")
      (value "470R")
      (footprint "eagle-import:0402")
      (libsource (lib "eagle-import") (part "R_0402"))
    )
    (comp (ref "R49")
      (value "470R")
      (footprint "eagle-import:0402")
      (libsource (lib "eagle-import") (part "R_0402"))
    )
    (comp (ref "R51")
      (value "470R")
      (footprint "eagle-import:0402")
      (libsource (lib "eagle-import") (part "R_0402"))
    )
    (comp (ref "R52")
      (value "470R")
      (footprint "eagle-import:0402")
      (libsource (lib "eagle-import") (part "R_0402"))
    )
    (comp (ref "R53")
      (value "470R")
      (footprint "eagle-import:0402")
      (libsource (lib "eagle-import") (part "R_0402"))
    )
    (comp (ref "R55")
      (value "470R")
      (footprint "eagle-import:0402")
      (libsource (lib "eagle-import") (part "R_0402"))
    )
    (comp (ref "R56")
      (value "470R")
      (footprint "eagle-import:0402")
      (libsource (lib "eagle-import") (part "R_0402"))
    )
    (comp (ref "R57")
      (value "470R")
      (footprint "eagle-import:0402")
      (libsource (lib "eagle-import") (part "R_0402"))
    )
    (comp (ref "R59")
      (value "470R")
      (footprint "eagle-import:0402")
      (libsource (lib "eagle-import") (part "R_0402"))
    )
    (comp (ref "R60")
      (value "470R")
      (footprint "eagle-import:0402")
      (libsource (lib "eagle-import") (part "R_0402"))
    )
    (comp (ref "R61")
      (value "470R")
      (footprint "eagle-import:0402")
      (libsource (lib "eagle-import") (part "R_0402"))
    )
    (comp (ref "R63")
      (value "470R")
      (footprint "eagle-import:0402")
      (libsource (lib "eagle-import") (part "R_0402"))
    )
    (comp (ref "R64")
      (value "470R")
      (footprint "eagle-import:0402")
      (libsource (lib "eagle-import") (part "R_0402"))
    )
    (comp (ref "R65")
      (value "470R")
      (footprint "eagle-import:0402")
      (libsource (lib "eagle-import") (part "R_0402"))
    )
    (comp (ref "R67")
      (value "470R")
      (footprint "eagle-import:0402")
      (libsource (lib "eagle-import") (part "R_0402"))
    )
    (comp (ref "R68")
      (value "470R")
      (footprint "eagle-import:0402")
      (libsource (lib "eagle-import") (part "R_0402"))
    )
    (comp (ref "R69")
      (value "470R")
      (footprint "eagle-import:0402")
      (libsource (lib "eagle-import") (part "R_0402"))
    )
    (comp (ref "R71")
      (value "470R")
      (footprint "eagle-import:0402")
      (libsource (lib "eagle-import") (part "R_0402"))
    )
    (comp (ref "R72")
      (value "470R")
      (footprint "eagle-import:0402")
      (libsource (lib "eagle-import") (part "R_0402"))
    )
    (comp (ref "R73")
      (value "470R")
      (footprint "eagle-import:0402")
      (libsource (lib "eagle-import") (part "R_0402"))
    )
    (comp (ref "R75")
      (value "470R")
      (footprint "eagle-import:0402")
      (libsource (lib "eagle-import") (part "R_0402"))
    )
    (comp (ref "R76")
      (value "470R")
      (footprint "eagle-import:0402")
      (libsource (lib "eagle-import") (part "R_0402"))
    )
    (comp (ref "R77")
      (value "470R")
      (footprint "eagle-import:0402")
      (libsource (lib "eagle-import") (part "R_0402"))
    )
    (comp (ref "R79")
      (value "470R")
      (footprint "eagle-import:0402")
      (libsource (lib "eagle-import") (part "R_0402"))
    )
    (comp (ref "R80")
      (value "470R")
      (footprint "eagle-import:0402")
      (libsource (lib "eagle-import") (part "R_0402"))
    )
    (comp (ref "R81")
      (value "470R")
      (footprint "eagle-import:0402")
      (libsource (lib "eagle-import") (part "R_0402"))
    )
    (comp (ref "R83")
      (value "470R")
      (footprint "eagle-import:0402")
      (libsource (lib "eagle-import") (part "R_0402"))
    )
    (comp (ref "R84")
      (value "470R")
      (footprint "eagle-import:0402")
      (libsource (lib "eagle-import") (part "R_0402"))
    )
    (comp (ref "R85")
      (value "470R")
      (footprint "eagle-import:0402")
      (libsource (lib "eagle-import") (part "R_0402"))
    )
    (comp (ref "R87")
      (value "470R")
      (footprint "eagle-import:0402")
      (libsource (lib "eagle-import") (part "R_0402"))
    )
    (comp (ref "R88")
      (value "470R")
      (footprint "eagle-import:0402")
      (libsource (lib "eagle-import") (part "R_0402"))
    )
    (comp (ref "R89")
      (value "470R")
      (footprint "eagle-import:0402")
      (libsource (lib "eagle-import") (part "R_0402"))
    )
    (comp (ref "R91")
      (value "470R")
      (footprint "eagle-import:0402")
      (libsource (lib "eagle-import") (part "R_0402"))
    )
    (comp (ref "R92")
      (value "470R")
      (footprint "eagle-import:0402")
      (libsource (lib "eagle-import") (part "R_0402"))
    )
    (comp (ref "R93")
      (value "470R")
      (footprint "eagle-import:0402")
      (libsource (lib "eagle-import") (part "R_0402"))
    )
    (comp (ref "R95")
      (value "470R")
      (footprint "eagle-import:0402")
      (libsource (lib "eagle-import") (part "R_0402"))
    )
    (comp (ref "R97")
      (value "470R")
      (footprint "eagle-import:0402")
      (libsource (lib "eagle-import") (part "R_0402"))
    )
    (comp (ref "R99")
      (value "470R")
      (footprint "eagle-import:0402")
      (libsource (lib "eagle-import") (part "R_0402"))
    )
    (comp (ref "RYS1")
      (value "1K")
      (footprint "eagle-import:0402")
      (libsource (lib "eagle-import") (part "R_0402"))
    )
    (comp (ref "RYS2")
      (value "1K")
      (footprint "eagle-import:0402")
      (libsource (lib "eagle-import") (part "R_0402"))
    )
    (comp (ref "RYS3")
      (value "1K")
      (footprint "eagle-import:0402")
      (libsource (lib "eagle-import") (part "R_0402"))
    )
    (comp (ref "RYS4")
      (value "1K")
      (footprint "eagle-import:0402")
      (libsource (lib "eagle-import") (part "R_0402"))
    )
    (comp (ref "RYS5")
      (value "1K")
      (footprint "eagle-import:0402")
      (libsource (lib "eagle-import") (part "R_0402"))
    )
    (comp (ref "RYS6")
      (value "1K")
      (footprint "eagle-import:0402")
      (libsource (lib "eagle-import") (part "R_0402"))
    )
    (comp (ref "RYS7")
      (value "1K")
      (footprint "eagle-import:0402")
      (libsource (lib "eagle-import") (part "R_0402"))
    )
    (comp (ref "RYS9")
      (value "1K")
      (footprint "eagle-import:0402")
      (libsource (lib "eagle-import") (part "R_0402"))
    )
    (comp (ref "RYS10")
      (value "1K")
      (footprint "eagle-import:0402")
      (libsource (lib "eagle-import") (part "R_0402"))
    )
    (comp (ref "RYS11")
      (value "1K")
      (footprint "eagle-import:0402")
      (libsource (lib "eagle-import") (part "R_0402"))
    )
    (comp (ref "RYS12")
      (value "1K")
      (footprint "eagle-import:0402")
      (libsource (lib "eagle-import") (part "R_0402"))
    )
    (comp (ref "RYS14")
      (value "1K")
      (footprint "eagle-import:0402")
      (libsource (lib "eagle-import") (part "R_0402"))
    )
    (comp (ref "RYS15")
      (value "1K")
      (footprint "eagle-import:0402")
      (libsource (lib "eagle-import") (part "R_0402"))
    )
    (comp (ref "RYS16")
      (value "1K")
      (footprint "eagle-import:0402")
      (libsource (lib "eagle-import") (part "R_0402"))
    )
    (comp (ref "RYS17")
      (value "1K")
      (footprint "eagle-import:0402")
      (libsource (lib "eagle-import") (part "R_0402"))
    )
    (comp (ref "RYS18")
      (value "1K")
      (footprint "eagle-import:0402")
      (libsource (lib "eagle-import") (part "R_0402"))
    )
    (comp (ref "RYS19")
      (value "1K")
      (footprint "eagle-import:0402")
      (libsource (lib "eagle-import") (part "R_0402"))
    )
    (comp (ref "RYS20")
      (value "1K")
      (footprint "eagle-import:0402")
      (libsource (lib "eagle-import") (part "R_0402"))
    )
    (comp (ref "RYS22")
      (value "1K")
      (footprint "eagle-import:0402")
      (libsource (lib "eagle-import") (part "R_0402"))
    )
    (comp (ref "RYS23")
      (value "1K")
      (footprint "eagle-import:0402")
      (libsource (lib "eagle-import") (part "R_0402"))
    )
    (comp (ref "RYS24")
      (value "1K")
      (footprint "eagle-import:0402")
      (libsource (lib "eagle-import") (part "R_0402"))
    )
    (comp (ref "RYS26")
      (value "1K")
      (footprint "eagle-import:0402")
      (libsource (lib "eagle-import") (part "R_0402"))
    )
    (comp (ref "RYS27")
      (value "1K")
      (footprint "eagle-import:0402")
      (libsource (lib "eagle-import") (part "R_0402"))
    )
    (comp (ref "RYS28")
      (value "1K")
      (footprint "eagle-import:0402")
      (libsource (lib "eagle-import") (part "R_0402"))
    )
    (comp (ref "RYS30")
      (value "1K")
      (footprint "eagle-import:0402")
      (libsource (lib "eagle-import") (part "R_0402"))
    )
    (comp (ref "RYS31")
      (value "1K")
      (footprint "eagle-import:0402")
      (libsource (lib "eagle-import") (part "R_0402"))
    )
    (comp (ref "RYS32")
      (value "1K")
      (footprint "eagle-import:0402")
      (libsource (lib "eagle-import") (part "R_0402"))
    )
    (comp (ref "RYS34")
      (value "1K")
      (footprint "eagle-import:0402")
      (libsource (lib "eagle-import") (part "R_0402"))
    )
    (comp (ref "RYS35")
      (value "1K")
      (footprint "eagle-import:0402")
      (libsource (lib "eagle-import") (part "R_0402"))
    )
    (comp (ref "RYS36")
      (value "1K")
      (footprint "eagle-import:0402")
      (libsource (lib "eagle-import") (part "R_0402"))
    )
    (comp (ref "RYS38")
      (value "1K")
      (footprint "eagle-import:0402")
      (libsource (lib "eagle-import") (part "R_0402"))
    )
    (comp (ref "RYS39")
      (value "1K")
      (footprint "eagle-import:0402")
      (libsource (lib "eagle-import") (part "R_0402"))
    )
    (comp (ref "RYS40")
      (value "1K")
      (footprint "eagle-import:0402")
      (libsource (lib "eagle-import") (part "R_0402"))
    )
    (comp (ref "RYS42")
      (value "1K")
      (footprint "eagle-import:0402")
      (libsource (lib "eagle-import") (part "R_0402"))
    )
    (comp (ref "RYS43")
      (value "1K")
      (footprint "eagle-import:0402")
      (libsource (lib "eagle-import") (part "R_0402"))
    )
    (comp (ref "RYS44")
      (value "1K")
      (footprint "eagle-import:0402")
      (libsource (lib "eagle-import") (part "R_0402"))
    )
    (comp (ref "RYS46")
      (value "1K")
      (footprint "eagle-import:0402")
      (libsource (lib "eagle-import") (part "R_0402"))
    )
    (comp (ref "RYS47")
      (value "1K")
      (footprint "eagle-import:0402")
      (libsource (lib "eagle-import") (part "R_0402"))
    )
    (comp (ref "RYS48")
      (value "1K")
      (footprint "eagle-import:0402")
      (libsource (lib "eagle-import") (part "R_0402"))
    )
    (comp (ref "RYS50")
      (value "1K")
      (footprint "eagle-import:0402")
      (libsource (lib "eagle-import") (part "R_0402"))
    )
    (comp (ref "RYS51")
      (value "1K")
      (footprint "eagle-import:0402")
      (libsource (lib "eagle-import") (part "R_0402"))
    )
    (comp (ref "RYS52")
      (value "1K")
      (footprint "eagle-import:0402")
      (libsource (lib "eagle-import") (part "R_0402"))
    )
    (comp (ref "RYS54")
      (value "1K")
      (footprint "eagle-import:0402")
      (libsource (lib "eagle-import") (part "R_0402"))
    )
    (comp (ref "RYS55")
      (value "1K")
      (footprint "eagle-import:0402")
      (libsource (lib "eagle-import") (part "R_0402"))
    )
    (comp (ref "RYS56")
      (value "1K")
      (footprint "eagle-import:0402")
      (libsource (lib "eagle-import") (part "R_0402"))
    )
    (comp (ref "RYS58")
      (value "1K")
      (footprint "eagle-import:0402")
      (libsource (lib "eagle-import") (part "R_0402"))
    )
    (comp (ref "RYS59")
      (value "1K")
      (footprint "eagle-import:0402")
      (libsource (lib "eagle-import") (part "R_0402"))
    )
    (comp (ref "RYS60")
      (value "1K")
      (footprint "eagle-import:0402")
      (libsource (lib "eagle-import") (part "R_0402"))
    )
    (comp (ref "RYS62")
      (value "1K")
      (footprint "eagle-import:0402")
      (libsource (lib "eagle-import") (part "R_0402"))
    )
    (comp (ref "RYS63")
      (value "1K")
      (footprint "eagle-import:0402")
      (libsource (lib "eagle-import") (part "R_0402"))
    )
    (comp (ref "RYS64")
      (value "1K")
      (footprint "eagle-import:0402")
      (libsource (lib "eagle-import") (part "R_0402"))
    )
    (comp (ref "RYS66")
      (value "1K")
      (footprint "eagle-import:0402")
      (libsource (lib "eagle-import") (part "R_0402"))
    )
    (comp (ref "RYS67")
      (value "1K")
      (footprint "eagle-import:0402")
      (libsource (lib "eagle-import") (part "R_0402"))
    )
    (comp (ref "RYS68")
      (value "1K")
      (footprint "eagle-import:0402")
      (libsource (lib "eagle-import") (part "R_0402"))
    )
    (comp (ref "RYS70")
      (value "1K")
      (footprint "eagle-import:0402")
      (libsource (lib "eagle-import") (part "R_0402"))
    )
    (comp (ref "RYS71")
      (value "1K")
      (footprint "eagle-import:0402")
      (libsource (lib "eagle-import") (part "R_0402"))
    )
    (comp (ref "RYS72")
      (value "1K")
      (footprint "eagle-import:0402")
      (libsource (lib "eagle-import") (part "R_0402"))
    )
    (comp (ref "RYS74")
      (value "1K")
      (footprint "eagle-import:0402")
      (libsource (lib "eagle-import") (part "R_0402"))
    )
    (comp (ref "RYS76")
      (value "1K")
      (footprint "eagle-import:0402")
      (libsource (lib "eagle-import") (part "R_0402"))
    )
    (comp (ref "RYS78")
      (value "1K")
      (footprint "eagle-import:0402")
      (libsource (lib "eagle-import") (part "R_0402"))
    )
    (comp (ref "SW1")
      (value "PTS810SJG250SMTRLFS")
      (footprint "eagle-import:PTS810")
      (fields (field (name "COPYRIGHT") "Copyright (C) 2018 Accelerated Designs. All rights reserved"))
      (libsource (lib "eagle-import") (part "PTS810SJG250SMTRLFS"))
    )
    (comp (ref "SW2")
      (value "PTS810SJG250SMTRLFS")
      (footprint "eagle-import:PTS810")
      (fields (field (name "COPYRIGHT") "Copyright (C) 2018 Accelerated Designs. All rights reserved"))
      (libsource (lib "eagle-import") (part "PTS810SJG250SMTRLFS"))
    )
    (comp (ref "SW3")
      (value "PTS810SJG250SMTRLFS")
      (footprint "eagle-import:PTS810")
      (fields (field (name "COPYRIGHT") "Copyright (C) 2018 Accelerated Designs. All rights reserved"))
      (libsource (lib "eagle-import") (part "PTS810SJG250SMTRLFS"))
    )
    (comp (ref "SW4")
      (value "PTS810SJG250SMTRLFS")
      (footprint "eagle-import:PTS810")
      (fields (field (name "COPYRIGHT") "Copyright (C) 2018 Accelerated Designs. All rights reserved"))
      (libsource (lib "eagle-import") (part "PTS810SJG250SMTRLFS"))
    )
    (comp (ref "U1")
      (value "BC846BW")
      (footprint "eagle-import:SOT323")
      (libsource (lib "eagle-import") (part "BC846BW"))
    )
    (comp (ref "U2")
      (value "BC846BW")
      (footprint "eagle-import:SOT323")
      (libsource (lib "eagle-import") (part "BC846BW"))
    )
    (comp (ref "U3")
      (value "BC846BW")
      (footprint "eagle-import:SOT323")
      (libsource (lib "eagle-import") (part "BC846BW"))
    )
    (comp (ref "U4")
      (value "BC846BW")
      (footprint "eagle-import:SOT323")
      (libsource (lib "eagle-import") (part "BC846BW"))
    )
    (comp (ref "U5")
      (value "BC846BW")
      (footprint "eagle-import:SOT323")
      (libsource (lib "eagle-import") (part "BC846BW"))
    )
    (comp (ref "U6")
      (value "BC846BW")
      (footprint "eagle-import:SOT323")
      (libsource (lib "eagle-import") (part "BC846BW"))
    )
    (comp (ref "U7")
      (value "BC846BW")
      (footprint "eagle-import:SOT323")
      (libsource (lib "eagle-import") (part "BC846BW"))
    )
    (comp (ref "U8")
      (value "BC846BW")
      (footprint "eagle-import:SOT323")
      (libsource (lib "eagle-import") (part "BC846BW"))
    )
    (comp (ref "U9")
      (value "BC846BW")
      (footprint "eagle-import:SOT323")
      (libsource (lib "eagle-import") (part "BC846BW"))
    )
    (comp (ref "U10")
      (value "BC846BW")
      (footprint "eagle-import:SOT323")
      (libsource (lib "eagle-import") (part "BC846BW"))
    )
    (comp (ref "U11")
      (value "BC846BW")
      (footprint "eagle-import:SOT323")
      (libsource (lib "eagle-import") (part "BC846BW"))
    )
    (comp (ref "U13")
      (value "BC846BW")
      (footprint "eagle-import:SOT323")
      (libsource (lib "eagle-import") (part "BC846BW"))
    )
    (comp (ref "U14")
      (value "BC846BW")
      (footprint "eagle-import:SOT323")
      (libsource (lib "eagle-import") (part "BC846BW"))
    )
    (comp (ref "U15")
      (value "BC846BW")
      (footprint "eagle-import:SOT323")
      (libsource (lib "eagle-import") (part "BC846BW"))
    )
    (comp (ref "U16")
      (value "BC846BW")
      (footprint "eagle-import:SOT323")
      (libsource (lib "eagle-import") (part "BC846BW"))
    )
    (comp (ref "U17")
      (value "BC846BW")
      (footprint "eagle-import:SOT323")
      (libsource (lib "eagle-import") (part "BC846BW"))
    )
    (comp (ref "U18")
      (value "BC846BW")
      (footprint "eagle-import:SOT323")
      (libsource (lib "eagle-import") (part "BC846BW"))
    )
    (comp (ref "U20")
      (value "BC846BW")
      (footprint "eagle-import:SOT323")
      (libsource (lib "eagle-import") (part "BC846BW"))
    )
    (comp (ref "U22")
      (value "BC846BW")
      (footprint "eagle-import:SOT323")
      (libsource (lib "eagle-import") (part "BC846BW"))
    )
    (comp (ref "U23")
      (value "BC846BW")
      (footprint "eagle-import:SOT323")
      (libsource (lib "eagle-import") (part "BC846BW"))
    )
    (comp (ref "U24")
      (value "BC846BW")
      (footprint "eagle-import:SOT323")
      (libsource (lib "eagle-import") (part "BC846BW"))
    )
    (comp (ref "U26")
      (value "BC846BW")
      (footprint "eagle-import:SOT323")
      (libsource (lib "eagle-import") (part "BC846BW"))
    )
    (comp (ref "U27")
      (value "BC846BW")
      (footprint "eagle-import:SOT323")
      (libsource (lib "eagle-import") (part "BC846BW"))
    )
    (comp (ref "U28")
      (value "BC846BW")
      (footprint "eagle-import:SOT323")
      (libsource (lib "eagle-import") (part "BC846BW"))
    )
    (comp (ref "U30")
      (value "BC846BW")
      (footprint "eagle-import:SOT323")
      (libsource (lib "eagle-import") (part "BC846BW"))
    )
    (comp (ref "U31")
      (value "BC846BW")
      (footprint "eagle-import:SOT323")
      (libsource (lib "eagle-import") (part "BC846BW"))
    )
    (comp (ref "U32")
      (value "BC846BW")
      (footprint "eagle-import:SOT323")
      (libsource (lib "eagle-import") (part "BC846BW"))
    )
    (comp (ref "U34")
      (value "BC846BW")
      (footprint "eagle-import:SOT323")
      (libsource (lib "eagle-import") (part "BC846BW"))
    )
    (comp (ref "U35")
      (value "BC846BW")
      (footprint "eagle-import:SOT323")
      (libsource (lib "eagle-import") (part "BC846BW"))
    )
    (comp (ref "U36")
      (value "BC846BW")
      (footprint "eagle-import:SOT323")
      (libsource (lib "eagle-import") (part "BC846BW"))
    )
    (comp (ref "U38")
      (value "BC846BW")
      (footprint "eagle-import:SOT323")
      (libsource (lib "eagle-import") (part "BC846BW"))
    )
    (comp (ref "U39")
      (value "BC846BW")
      (footprint "eagle-import:SOT323")
      (libsource (lib "eagle-import") (part "BC846BW"))
    )
    (comp (ref "U40")
      (value "BC846BW")
      (footprint "eagle-import:SOT323")
      (libsource (lib "eagle-import") (part "BC846BW"))
    )
    (comp (ref "U42")
      (value "BC846BW")
      (footprint "eagle-import:SOT323")
      (libsource (lib "eagle-import") (part "BC846BW"))
    )
    (comp (ref "U43")
      (value "BC846BW")
      (footprint "eagle-import:SOT323")
      (libsource (lib "eagle-import") (part "BC846BW"))
    )
    (comp (ref "U44")
      (value "BC846BW")
      (footprint "eagle-import:SOT323")
      (libsource (lib "eagle-import") (part "BC846BW"))
    )
    (comp (ref "U46")
      (value "BC846BW")
      (footprint "eagle-import:SOT323")
      (libsource (lib "eagle-import") (part "BC846BW"))
    )
    (comp (ref "U47")
      (value "BC846BW")
      (footprint "eagle-import:SOT323")
      (libsource (lib "eagle-import") (part "BC846BW"))
    )
    (comp (ref "U48")
      (value "BC846BW")
      (footprint "eagle-import:SOT323")
      (libsource (lib "eagle-import") (part "BC846BW"))
    )
    (comp (ref "U50")
      (value "BC846BW")
      (footprint "eagle-import:SOT323")
      (libsource (lib "eagle-import") (part "BC846BW"))
    )
    (comp (ref "U51")
      (value "BC846BW")
      (footprint "eagle-import:SOT323")
      (libsource (lib "eagle-import") (part "BC846BW"))
    )
    (comp (ref "U52")
      (value "BC846BW")
      (footprint "eagle-import:SOT323")
      (libsource (lib "eagle-import") (part "BC846BW"))
    )
    (comp (ref "U54")
      (value "BC846BW")
      (footprint "eagle-import:SOT323")
      (libsource (lib "eagle-import") (part "BC846BW"))
    )
    (comp (ref "U55")
      (value "BC846BW")
      (footprint "eagle-import:SOT323")
      (libsource (lib "eagle-import") (part "BC846BW"))
    )
    (comp (ref "U56")
      (value "BC846BW")
      (footprint "eagle-import:SOT323")
      (libsource (lib "eagle-import") (part "BC846BW"))
    )
    (comp (ref "U58")
      (value "BC846BW")
      (footprint "eagle-import:SOT323")
      (libsource (lib "eagle-import") (part "BC846BW"))
    )
    (comp (ref "U59")
      (value "BC846BW")
      (footprint "eagle-import:SOT323")
      (libsource (lib "eagle-import") (part "BC846BW"))
    )
    (comp (ref "U60")
      (value "BC846BW")
      (footprint "eagle-import:SOT323")
      (libsource (lib "eagle-import") (part "BC846BW"))
    )
    (comp (ref "U62")
      (value "BC846BW")
      (footprint "eagle-import:SOT323")
      (libsource (lib "eagle-import") (part "BC846BW"))
    )
    (comp (ref "U63")
      (value "BC846BW")
      (footprint "eagle-import:SOT323")
      (libsource (lib "eagle-import") (part "BC846BW"))
    )
    (comp (ref "U64")
      (value "BC846BW")
      (footprint "eagle-import:SOT323")
      (libsource (lib "eagle-import") (part "BC846BW"))
    )
    (comp (ref "U66")
      (value "BC846BW")
      (footprint "eagle-import:SOT323")
      (libsource (lib "eagle-import") (part "BC846BW"))
    )
    (comp (ref "U67")
      (value "BC846BW")
      (footprint "eagle-import:SOT323")
      (libsource (lib "eagle-import") (part "BC846BW"))
    )
    (comp (ref "U68")
      (value "BC846BW")
      (footprint "eagle-import:SOT323")
      (libsource (lib "eagle-import") (part "BC846BW"))
    )
    (comp (ref "U70")
      (value "BC846BW")
      (footprint "eagle-import:SOT323")
      (libsource (lib "eagle-import") (part "BC846BW"))
    )
    (comp (ref "U71")
      (value "BC846BW")
      (footprint "eagle-import:SOT323")
      (libsource (lib "eagle-import") (part "BC846BW"))
    )
    (comp (ref "U72")
      (value "BC846BW")
      (footprint "eagle-import:SOT323")
      (libsource (lib "eagle-import") (part "BC846BW"))
    )
    (comp (ref "U74")
      (value "BC846BW")
      (footprint "eagle-import:SOT323")
      (libsource (lib "eagle-import") (part "BC846BW"))
    )
    (comp (ref "U76")
      (value "BC846BW")
      (footprint "eagle-import:SOT323")
      (libsource (lib "eagle-import") (part "BC846BW"))
    )
    (comp (ref "U78")
      (value "BC846BW")
      (footprint "eagle-import:SOT323")
      (libsource (lib "eagle-import") (part "BC846BW"))
    )
  )
  (nets
    (net (code "1") (name "GND") (class "Default")
      (node (ref "J1") (pin "1") (pinfunction "1_1") (pintype "passive"))
      (node (ref "J1") (pin "2") (pinfunction "2_2") (pintype "passive"))
      (node (ref "LED18") (pin "C") (pinfunction "C_C") (pintype "passive"))
      (node (ref "LED19") (pin "C") (pinfunction "C_C") (pintype "passive"))
      (node (ref "LED20") (pin "C") (pinfunction "C_C") (pintype "passive"))
      (node (ref "LED21") (pin "C") (pinfunction "C_C") (pintype "passive"))
      (node (ref "LED3") (pin "C") (pinfunction "C_C") (pintype "passive"))
      (node (ref "U1") (pin "2") (pinfunction "E(1)_2") (pintype "output"))
      (node (ref "U10") (pin "2") (pinfunction "E(1)_2") (pintype "output"))
      (node (ref "U11") (pin "2") (pinfunction "E(1)_2") (pintype "output"))
      (node (ref "U13") (pin "2") (pinfunction "E(1)_2") (pintype "output"))
      (node (ref "U14") (pin "2") (pinfunction "E(1)_2") (pintype "output"))
      (node (ref "U15") (pin "2") (pinfunction "E(1)_2") (pintype "output"))
      (node (ref "U16") (pin "2") (pinfunction "E(1)_2") (pintype "output"))
      (node (ref "U17") (pin "2") (pinfunction "E(1)_2") (pintype "output"))
      (node (ref "U18") (pin "2") (pinfunction "E(1)_2") (pintype "output"))
      (node (ref "U2") (pin "2") (pinfunction "E(1)_2") (pintype "output"))
      (node (ref "U20") (pin "2") (pinfunction "E(1)_2") (pintype "output"))
      (node (ref "U22") (pin "2") (pinfunction "E(1)_2") (pintype "output"))
      (node (ref "U23") (pin "2") (pinfunction "E(1)_2") (pintype "output"))
      (node (ref "U24") (pin "2") (pinfunction "E(1)_2") (pintype "output"))
      (node (ref "U26") (pin "2") (pinfunction "E(1)_2") (pintype "output"))
      (node (ref "U27") (pin "2") (pinfunction "E(1)_2") (pintype "output"))
      (node (ref "U28") (pin "2") (pinfunction "E(1)_2") (pintype "output"))
      (node (ref "U3") (pin "2") (pinfunction "E(1)_2") (pintype "output"))
      (node (ref "U30") (pin "2") (pinfunction "E(1)_2") (pintype "output"))
      (node (ref "U31") (pin "2") (pinfunction "E(1)_2") (pintype "output"))
      (node (ref "U32") (pin "2") (pinfunction "E(1)_2") (pintype "output"))
      (node (ref "U34") (pin "2") (pinfunction "E(1)_2") (pintype "output"))
      (node (ref "U35") (pin "2") (pinfunction "E(1)_2") (pintype "output"))
      (node (ref "U36") (pin "2") (pinfunction "E(1)_2") (pintype "output"))
      (node (ref "U38") (pin "2") (pinfunction "E(1)_2") (pintype "output"))
      (node (ref "U39") (pin "2") (pinfunction "E(1)_2") (pintype "output"))
      (node (ref "U4") (pin "2") (pinfunction "E(1)_2") (pintype "output"))
      (node (ref "U40") (pin "2") (pinfunction "E(1)_2") (pintype "output"))
      (node (ref "U42") (pin "2") (pinfunction "E(1)_2") (pintype "output"))
      (node (ref "U43") (pin "2") (pinfunction "E(1)_2") (pintype "output"))
      (node (ref "U44") (pin "2") (pinfunction "E(1)_2") (pintype "output"))
      (node (ref "U46") (pin "2") (pinfunction "E(1)_2") (pintype "output"))
      (node (ref "U47") (pin "2") (pinfunction "E(1)_2") (pintype "output"))
      (node (ref "U48") (pin "2") (pinfunction "E(1)_2") (pintype "output"))
      (node (ref "U5") (pin "2") (pinfunction "E(1)_2") (pintype "output"))
      (node (ref "U50") (pin "2") (pinfunction "E(1)_2") (pintype "output"))
      (node (ref "U51") (pin "2") (pinfunction "E(1)_2") (pintype "output"))
      (node (ref "U52") (pin "2") (pinfunction "E(1)_2") (pintype "output"))
      (node (ref "U54") (pin "2") (pinfunction "E(1)_2") (pintype "output"))
      (node (ref "U55") (pin "2") (pinfunction "E(1)_2") (pintype "output"))
      (node (ref "U56") (pin "2") (pinfunction "E(1)_2") (pintype "output"))
      (node (ref "U58") (pin "2") (pinfunction "E(1)_2") (pintype "output"))
      (node (ref "U59") (pin "2") (pinfunction "E(1)_2") (pintype "output"))
      (node (ref "U6") (pin "2") (pinfunction "E(1)_2") (pintype "output"))
      (node (ref "U60") (pin "2") (pinfunction "E(1)_2") (pintype "output"))
      (node (ref "U62") (pin "2") (pinfunction "E(1)_2") (pintype "output"))
      (node (ref "U63") (pin "2") (pinfunction "E(1)_2") (pintype "output"))
      (node (ref "U64") (pin "2") (pinfunction "E(1)_2") (pintype "output"))
      (node (ref "U66") (pin "2") (pinfunction "E(1)_2") (pintype "output"))
      (node (ref "U67") (pin "2") (pinfunction "E(1)_2") (pintype "output"))
      (node (ref "U68") (pin "2") (pinfunction "E(1)_2") (pintype "output"))
      (node (ref "U7") (pin "2") (pinfunction "E(1)_2") (pintype "output"))
      (node (ref "U70") (pin "2") (pinfunction "E(1)_2") (pintype "output"))
      (node (ref "U71") (pin "2") (pinfunction "E(1)_2") (pintype "output"))
      (node (ref "U72") (pin "2") (pinfunction "E(1)_2") (pintype "output"))
      (node (ref "U74") (pin "2") (pinfunction "E(1)_2") (pintype "output"))
      (node (ref "U76") (pin "2") (pinfunction "E(1)_2") (pintype "output"))
      (node (ref "U78") (pin "2") (pinfunction "E(1)_2") (pintype "output"))
      (node (ref "U8") (pin "2") (pinfunction "E(1)_2") (pintype "output"))
      (node (ref "U9") (pin "2") (pinfunction "E(1)_2") (pintype "output"))
    )
    (net (code "2") (name "GNDE") (class "Default")
      (node (ref "J1") (pin "10") (pinfunction "10_10") (pintype "passive"))
      (node (ref "J1") (pin "9") (pinfunction "9_9") (pintype "passive"))
    )
    (net (code "3") (name "IIC_1_SCL") (class "Default")
      (node (ref "J10") (pin "P$5") (pinfunction "P$5_P$5") (pintype "bidirectional"))
      (node (ref "RYS44") (pin "P$1") (pinfunction "1_P$1") (pintype "passive"))
    )
    (net (code "4") (name "IIC_1_SDA") (class "Default")
      (node (ref "J10") (pin "P$6") (pinfunction "P$6_P$6") (pintype "bidirectional"))
      (node (ref "RYS3") (pin "P$1") (pinfunction "1_P$1") (pintype "passive"))
    )
    (net (code "5") (name "INT_MI_01") (class "Default")
      (node (ref "J10") (pin "P$39") (pinfunction "P$39_P$39") (pintype "bidirectional"))
      (node (ref "RYS78") (pin "P$1") (pinfunction "1_P$1") (pintype "passive"))
    )
    (net (code "6") (name "INT_MI_02") (class "Default")
      (node (ref "J10") (pin "P$40") (pinfunction "P$40_P$40") (pintype "bidirectional"))
      (node (ref "RYS38") (pin "P$1") (pinfunction "1_P$1") (pintype "passive"))
    )
    (net (code "7") (name "INT_MI_03") (class "Default")
      (node (ref "J10") (pin "P$9") (pinfunction "P$9_P$9") (pintype "bidirectional"))
      (node (ref "RYS48") (pin "P$1") (pinfunction "1_P$1") (pintype "passive"))
    )
    (net (code "8") (name "INT_MI_04") (class "Default")
      (node (ref "J10") (pin "P$10") (pinfunction "P$10_P$10") (pintype "bidirectional"))
      (node (ref "RYS7") (pin "P$1") (pinfunction "1_P$1") (pintype "passive"))
    )
    (net (code "9") (name "INT_MI_05") (class "Default")
      (node (ref "J10") (pin "P$1") (pinfunction "P$1_P$1") (pintype "bidirectional"))
      (node (ref "RYS40") (pin "P$1") (pinfunction "1_P$1") (pintype "passive"))
    )
    (net (code "10") (name "J2_1") (class "Default")
      (node (ref "J2") (pin "1") (pinfunction "1_1") (pintype "passive"))
      (node (ref "RYS35") (pin "P$1") (pinfunction "1_P$1") (pintype "passive"))
    )
    (net (code "11") (name "J2_2") (class "Default")
      (node (ref "J2") (pin "2") (pinfunction "2_2") (pintype "passive"))
      (node (ref "RYS55") (pin "P$1") (pinfunction "1_P$1") (pintype "passive"))
    )
    (net (code "12") (name "J2_3") (class "Default")
      (node (ref "J2") (pin "3") (pinfunction "3_3") (pintype "passive"))
      (node (ref "RYS39") (pin "P$1") (pinfunction "1_P$1") (pintype "passive"))
    )
    (net (code "13") (name "J2_4") (class "Default")
      (node (ref "J2") (pin "4") (pinfunction "4_4") (pintype "passive"))
      (node (ref "RYS59") (pin "P$1") (pinfunction "1_P$1") (pintype "passive"))
    )
    (net (code "14") (name "J2_5") (class "Default")
      (node (ref "J2") (pin "5") (pinfunction "5_5") (pintype "passive"))
      (node (ref "RYS43") (pin "P$1") (pinfunction "1_P$1") (pintype "passive"))
    )
    (net (code "15") (name "J2_6") (class "Default")
      (node (ref "J2") (pin "6") (pinfunction "6_6") (pintype "passive"))
      (node (ref "RYS63") (pin "P$1") (pinfunction "1_P$1") (pintype "passive"))
    )
    (net (code "16") (name "J2_7") (class "Default")
      (node (ref "J2") (pin "7") (pinfunction "7_7") (pintype "passive"))
      (node (ref "RYS47") (pin "P$1") (pinfunction "1_P$1") (pintype "passive"))
    )
    (net (code "17") (name "J2_8") (class "Default")
      (node (ref "J2") (pin "8") (pinfunction "8_8") (pintype "passive"))
      (node (ref "RYS67") (pin "P$1") (pinfunction "1_P$1") (pintype "passive"))
    )
    (net (code "18") (name "J2_9") (class "Default")
      (node (ref "J2") (pin "9") (pinfunction "9_9") (pintype "passive"))
      (node (ref "RYS51") (pin "P$1") (pinfunction "1_P$1") (pintype "passive"))
    )
    (net (code "19") (name "J2_10") (class "Default")
      (node (ref "J2") (pin "10") (pinfunction "10_10") (pintype "passive"))
      (node (ref "RYS71") (pin "P$1") (pinfunction "1_P$1") (pintype "passive"))
    )
    (net (code "20") (name "J3_1") (class "Default")
      (node (ref "J3") (pin "1") (pinfunction "1_1") (pintype "passive"))
      (node (ref "RYS4") (pin "P$1") (pinfunction "1_P$1") (pintype "passive"))
    )
    (net (code "21") (name "J3_2") (class "Default")
      (node (ref "J3") (pin "2") (pinfunction "2_2") (pintype "passive"))
      (node (ref "RYS9") (pin "P$1") (pinfunction "1_P$1") (pintype "passive"))
    )
    (net (code "22") (name "J3_3") (class "Default")
      (node (ref "J3") (pin "3") (pinfunction "3_3") (pintype "passive"))
      (node (ref "RYS6") (pin "P$1") (pinfunction "1_P$1") (pintype "passive"))
    )
    (net (code "23") (name "J3_4") (class "Default")
      (node (ref "J3") (pin "4") (pinfunction "4_4") (pintype "passive"))
      (node (ref "RYS17") (pin "P$1") (pinfunction "1_P$1") (pintype "passive"))
    )
    (net (code "24") (name "J3_5") (class "Default")
      (node (ref "J3") (pin "5") (pinfunction "5_5") (pintype "passive"))
      (node (ref "RYS11") (pin "P$1") (pinfunction "1_P$1") (pintype "passive"))
    )
    (net (code "25") (name "J3_6") (class "Default")
      (node (ref "J3") (pin "6") (pinfunction "6_6") (pintype "passive"))
      (node (ref "RYS23") (pin "P$1") (pinfunction "1_P$1") (pintype "passive"))
    )
    (net (code "26") (name "J3_7") (class "Default")
      (node (ref "J3") (pin "7") (pinfunction "7_7") (pintype "passive"))
      (node (ref "RYS19") (pin "P$1") (pinfunction "1_P$1") (pintype "passive"))
    )
    (net (code "27") (name "J3_8") (class "Default")
      (node (ref "J3") (pin "8") (pinfunction "8_8") (pintype "passive"))
      (node (ref "RYS27") (pin "P$1") (pinfunction "1_P$1") (pintype "passive"))
    )
    (net (code "28") (name "J3_9") (class "Default")
      (node (ref "J3") (pin "9") (pinfunction "9_9") (pintype "passive"))
      (node (ref "RYS15") (pin "P$1") (pinfunction "1_P$1") (pintype "passive"))
    )
    (net (code "29") (name "J3_10") (class "Default")
      (node (ref "J3") (pin "10") (pinfunction "10_10") (pintype "passive"))
      (node (ref "RYS31") (pin "P$1") (pinfunction "1_P$1") (pintype "passive"))
    )
    (net (code "30") (name "Net-(J5-PadP$1)") (class "Default")
      (node (ref "J5") (pin "P$1") (pinfunction "P$1_P$1") (pintype "bidirectional"))
      (node (ref "LED6") (pin "C") (pinfunction "C_C") (pintype "passive"))
    )
    (net (code "31") (name "Net-(J5-PadP$2)") (class "Default")
      (node (ref "J5") (pin "P$2") (pinfunction "P$2_P$2") (pintype "bidirectional"))
      (node (ref "LED7") (pin "C") (pinfunction "C_C") (pintype "passive"))
    )
    (net (code "32") (name "Net-(J5-PadP$3)") (class "Default")
      (node (ref "J5") (pin "P$3") (pinfunction "P$3_P$3") (pintype "bidirectional"))
      (node (ref "LED8") (pin "C") (pinfunction "C_C") (pintype "passive"))
    )
    (net (code "33") (name "Net-(J5-PadP$4)") (class "Default")
      (node (ref "J5") (pin "P$4") (pinfunction "P$4_P$4") (pintype "bidirectional"))
      (node (ref "LED9") (pin "C") (pinfunction "C_C") (pintype "passive"))
    )
    (net (code "34") (name "Net-(J6-PadP$1)") (class "Default")
      (node (ref "J6") (pin "P$1") (pinfunction "P$1_P$1") (pintype "bidirectional"))
      (node (ref "LED1") (pin "C") (pinfunction "C_C") (pintype "passive"))
    )
    (net (code "35") (name "Net-(J6-PadP$2)") (class "Default")
      (node (ref "J6") (pin "P$2") (pinfunction "P$2_P$2") (pintype "bidirectional"))
      (node (ref "LED2") (pin "C") (pinfunction "C_C") (pintype "passive"))
    )
    (net (code "36") (name "Net-(J6-PadP$3)") (class "Default")
      (node (ref "J6") (pin "P$3") (pinfunction "P$3_P$3") (pintype "bidirectional"))
      (node (ref "LED4") (pin "C") (pinfunction "C_C") (pintype "passive"))
    )
    (net (code "37") (name "Net-(J6-PadP$4)") (class "Default")
      (node (ref "J6") (pin "P$4") (pinfunction "P$4_P$4") (pintype "bidirectional"))
      (node (ref "LED5") (pin "C") (pinfunction "C_C") (pintype "passive"))
    )
    (net (code "38") (name "Net-(J13-PadP$1)") (class "Default")
      (node (ref "J13") (pin "P$1") (pinfunction "P$1_P$1") (pintype "bidirectional"))
      (node (ref "LED10") (pin "C") (pinfunction "C_C") (pintype "passive"))
    )
    (net (code "39") (name "Net-(J13-PadP$2)") (class "Default")
      (node (ref "J13") (pin "P$2") (pinfunction "P$2_P$2") (pintype "bidirectional"))
      (node (ref "LED11") (pin "C") (pinfunction "C_C") (pintype "passive"))
    )
    (net (code "40") (name "Net-(J13-PadP$3)") (class "Default")
      (node (ref "J13") (pin "P$3") (pinfunction "P$3_P$3") (pintype "bidirectional"))
      (node (ref "LED12") (pin "C") (pinfunction "C_C") (pintype "passive"))
    )
    (net (code "41") (name "Net-(J13-PadP$4)") (class "Default")
      (node (ref "J13") (pin "P$4") (pinfunction "P$4_P$4") (pintype "bidirectional"))
      (node (ref "LED13") (pin "C") (pinfunction "C_C") (pintype "passive"))
    )
    (net (code "42") (name "Net-(J14-PadP$1)") (class "Default")
      (node (ref "J14") (pin "P$1") (pinfunction "P$1_P$1") (pintype "bidirectional"))
      (node (ref "LED14") (pin "C") (pinfunction "C_C") (pintype "passive"))
    )
    (net (code "43") (name "Net-(J14-PadP$2)") (class "Default")
      (node (ref "J14") (pin "P$2") (pinfunction "P$2_P$2") (pintype "bidirectional"))
      (node (ref "LED15") (pin "C") (pinfunction "C_C") (pintype "passive"))
    )
    (net (code "44") (name "Net-(J14-PadP$3)") (class "Default")
      (node (ref "J14") (pin "P$3") (pinfunction "P$3_P$3") (pintype "bidirectional"))
      (node (ref "LED16") (pin "C") (pinfunction "C_C") (pintype "passive"))
    )
    (net (code "45") (name "Net-(J14-PadP$4)") (class "Default")
      (node (ref "J14") (pin "P$4") (pinfunction "P$4_P$4") (pintype "bidirectional"))
      (node (ref "LED17") (pin "C") (pinfunction "C_C") (pintype "passive"))
    )
    (net (code "46") (name "Net-(R1-2)") (class "Default")
      (node (ref "LED1") (pin "A") (pinfunction "A_A") (pintype "passive"))
      (node (ref "R1") (pin "P$2") (pinfunction "2_P$2") (pintype "passive"))
    )
    (net (code "47") (name "Net-(R2-2)") (class "Default")
      (node (ref "LED2") (pin "A") (pinfunction "A_A") (pintype "passive"))
      (node (ref "R2") (pin "P$2") (pinfunction "2_P$2") (pintype "passive"))
    )
    (net (code "48") (name "Net-(R3-2)") (class "Default")
      (node (ref "LED4") (pin "A") (pinfunction "A_A") (pintype "passive"))
      (node (ref "R3") (pin "P$2") (pinfunction "2_P$2") (pintype "passive"))
    )
    (net (code "49") (name "Net-(R4-2)") (class "Default")
      (node (ref "LED5") (pin "A") (pinfunction "A_A") (pintype "passive"))
      (node (ref "R4") (pin "P$2") (pinfunction "2_P$2") (pintype "passive"))
    )
    (net (code "50") (name "Net-(R5-2)") (class "Default")
      (node (ref "LED6") (pin "A") (pinfunction "A_A") (pintype "passive"))
      (node (ref "R5") (pin "P$2") (pinfunction "2_P$2") (pintype "passive"))
    )
    (net (code "51") (name "Net-(R6-2)") (class "Default")
      (node (ref "LED7") (pin "A") (pinfunction "A_A") (pintype "passive"))
      (node (ref "R6") (pin "P$2") (pinfunction "2_P$2") (pintype "passive"))
    )
    (net (code "52") (name "Net-(R7-2)") (class "Default")
      (node (ref "LED8") (pin "A") (pinfunction "A_A") (pintype "passive"))
      (node (ref "R7") (pin "P$2") (pinfunction "2_P$2") (pintype "passive"))
    )
    (net (code "53") (name "Net-(R8-2)") (class "Default")
      (node (ref "LED9") (pin "A") (pinfunction "A_A") (pintype "passive"))
      (node (ref "R8") (pin "P$2") (pinfunction "2_P$2") (pintype "passive"))
    )
    (net (code "54") (name "Net-(R9-2)") (class "Default")
      (node (ref "LED10") (pin "A") (pinfunction "A_A") (pintype "passive"))
      (node (ref "R9") (pin "P$2") (pinfunction "2_P$2") (pintype "passive"))
    )
    (net (code "55") (name "Net-(R10-2)") (class "Default")
      (node (ref "LED11") (pin "A") (pinfunction "A_A") (pintype "passive"))
      (node (ref "R10") (pin "P$2") (pinfunction "2_P$2") (pintype "passive"))
    )
    (net (code "56") (name "Net-(R11-2)") (class "Default")
      (node (ref "LED12") (pin "A") (pinfunction "A_A") (pintype "passive"))
      (node (ref "R11") (pin "P$2") (pinfunction "2_P$2") (pintype "passive"))
    )
    (net (code "57") (name "Net-(R12-2)") (class "Default")
      (node (ref "LED13") (pin "A") (pinfunction "A_A") (pintype "passive"))
      (node (ref "R12") (pin "P$2") (pinfunction "2_P$2") (pintype "passive"))
    )
    (net (code "58") (name "Net-(R13-1)") (class "Default")
      (node (ref "LED3") (pin "A") (pinfunction "A_A") (pintype "passive"))
      (node (ref "R13") (pin "P$1") (pinfunction "1_P$1") (pintype "passive"))
    )
    (net (code "59") (name "Net-(R14-2)") (class "Default")
      (node (ref "LED14") (pin "A") (pinfunction "A_A") (pintype "passive"))
      (node (ref "R14") (pin "P$2") (pinfunction "2_P$2") (pintype "passive"))
    )
    (net (code "60") (name "Net-(R15-2)") (class "Default")
      (node (ref "LED15") (pin "A") (pinfunction "A_A") (pintype "passive"))
      (node (ref "R15") (pin "P$2") (pinfunction "2_P$2") (pintype "passive"))
    )
    (net (code "61") (name "Net-(R16-2)") (class "Default")
      (node (ref "LED16") (pin "A") (pinfunction "A_A") (pintype "passive"))
      (node (ref "R16") (pin "P$2") (pinfunction "2_P$2") (pintype "passive"))
    )
    (net (code "62") (name "Net-(R17-2)") (class "Default")
      (node (ref "LED17") (pin "A") (pinfunction "A_A") (pintype "passive"))
      (node (ref "R17") (pin "P$2") (pinfunction "2_P$2") (pintype "passive"))
    )
    (net (code "63") (name "Net-(R18-1)") (class "Default")
      (node (ref "LED18") (pin "A") (pinfunction "A_A") (pintype "passive"))
      (node (ref "R18") (pin "P$1") (pinfunction "1_P$1") (pintype "passive"))
    )
    (net (code "64") (name "Net-(R18-2)") (class "Default")
      (node (ref "R18") (pin "P$2") (pinfunction "2_P$2") (pintype "passive"))
      (node (ref "SW1") (pin "4") (pinfunction "4_4") (pintype "passive"))
    )
    (net (code "65") (name "Net-(R19-1)") (class "Default")
      (node (ref "LED19") (pin "A") (pinfunction "A_A") (pintype "passive"))
      (node (ref "R19") (pin "P$1") (pinfunction "1_P$1") (pintype "passive"))
    )
    (net (code "66") (name "Net-(R19-2)") (class "Default")
      (node (ref "R19") (pin "P$2") (pinfunction "2_P$2") (pintype "passive"))
      (node (ref "SW2") (pin "4") (pinfunction "4_4") (pintype "passive"))
    )
    (net (code "67") (name "Net-(R20-1)") (class "Default")
      (node (ref "LED20") (pin "A") (pinfunction "A_A") (pintype "passive"))
      (node (ref "R20") (pin "P$1") (pinfunction "1_P$1") (pintype "passive"))
    )
    (net (code "68") (name "Net-(R20-2)") (class "Default")
      (node (ref "R20") (pin "P$2") (pinfunction "2_P$2") (pintype "passive"))
      (node (ref "SW3") (pin "4") (pinfunction "4_4") (pintype "passive"))
    )
    (net (code "69") (name "Net-(R21-1)") (class "Default")
      (node (ref "LED21") (pin "A") (pinfunction "A_A") (pintype "passive"))
      (node (ref "R21") (pin "P$1") (pinfunction "1_P$1") (pintype "passive"))
    )
    (net (code "70") (name "Net-(R21-2)") (class "Default")
      (node (ref "R21") (pin "P$2") (pinfunction "2_P$2") (pintype "passive"))
      (node (ref "SW4") (pin "4") (pinfunction "4_4") (pintype "passive"))
    )
    (net (code "71") (name "Net-(R22-1)") (class "Default")
      (node (ref "J15") (pin "P$1") (pinfunction "P$1_P$1") (pintype "bidirectional"))
      (node (ref "R22") (pin "P$1") (pinfunction "1_P$1") (pintype "passive"))
    )
    (net (code "72") (name "Net-(R22-2)") (class "Default")
      (node (ref "R22") (pin "P$2") (pinfunction "2_P$2") (pintype "passive"))
      (node (ref "SW1") (pin "3") (pinfunction "3_3") (pintype "passive"))
    )
    (net (code "73") (name "Net-(R23-1)") (class "Default")
      (node (ref "LED23") (pin "A") (pinfunction "A_A") (pintype "passive"))
      (node (ref "R23") (pin "P$1") (pinfunction "1_P$1") (pintype "passive"))
    )
    (net (code "74") (name "Net-(R24-1)") (class "Default")
      (node (ref "LED24") (pin "A") (pinfunction "A_A") (pintype "passive"))
      (node (ref "R24") (pin "P$1") (pinfunction "1_P$1") (pintype "passive"))
    )
    (net (code "75") (name "Net-(R25-1)") (class "Default")
      (node (ref "LED25") (pin "A") (pinfunction "A_A") (pintype "passive"))
      (node (ref "R25") (pin "P$1") (pinfunction "1_P$1") (pintype "passive"))
    )
    (net (code "76") (name "Net-(R26-1)") (class "Default")
      (node (ref "LED26") (pin "A") (pinfunction "A_A") (pintype "passive"))
      (node (ref "R26") (pin "P$1") (pinfunction "1_P$1") (pintype "passive"))
    )
    (net (code "77") (name "Net-(R27-1)") (class "Default")
      (node (ref "LED27") (pin "A") (pinfunction "A_A") (pintype "passive"))
      (node (ref "R27") (pin "P$1") (pinfunction "1_P$1") (pintype "passive"))
    )
    (net (code "78") (name "Net-(R28-1)") (class "Default")
      (node (ref "LED28") (pin "A") (pinfunction "A_A") (pintype "passive"))
      (node (ref "R28") (pin "P$1") (pinfunction "1_P$1") (pintype "passive"))
    )
    (net (code "79") (name "Net-(R29-1)") (class "Default")
      (node (ref "LED29") (pin "A") (pinfunction "A_A") (pintype "passive"))
      (node (ref "R29") (pin "P$1") (pinfunction "1_P$1") (pintype "passive"))
    )
    (net (code "80") (name "Net-(R30-1)") (class "Default")
      (node (ref "LED30") (pin "A") (pinfunction "A_A") (pintype "passive"))
      (node (ref "R30") (pin "P$1") (pinfunction "1_P$1") (pintype "passive"))
    )
    (net (code "81") (name "Net-(R31-1)") (class "Default")
      (node (ref "LED31") (pin "A") (pinfunction "A_A") (pintype "passive"))
      (node (ref "R31") (pin "P$1") (pinfunction "1_P$1") (pintype "passive"))
    )
    (net (code "82") (name "Net-(R32-1)") (class "Default")
      (node (ref "LED32") (pin "A") (pinfunction "A_A") (pintype "passive"))
      (node (ref "R32") (pin "P$1") (pinfunction "1_P$1") (pintype "passive"))
    )
    (net (code "83") (name "Net-(R33-1)") (class "Default")
      (node (ref "LED33") (pin "A") (pinfunction "A_A") (pintype "passive"))
      (node (ref "R33") (pin "P$1") (pinfunction "1_P$1") (pintype "passive"))
    )
    (net (code "84") (name "Net-(R34-1)") (class "Default")
      (node (ref "J15") (pin "P$2") (pinfunction "P$2_P$2") (pintype "bidirectional"))
      (node (ref "R34") (pin "P$1") (pinfunction "1_P$1") (pintype "passive"))
    )
    (net (code "85") (name "Net-(R34-2)") (class "Default")
      (node (ref "R34") (pin "P$2") (pinfunction "2_P$2") (pintype "passive"))
      (node (ref "SW2") (pin "3") (pinfunction "3_3") (pintype "passive"))
    )
    (net (code "86") (name "Net-(R35-1)") (class "Default")
      (node (ref "LED35") (pin "A") (pinfunction "A_A") (pintype "passive"))
      (node (ref "R35") (pin "P$1") (pinfunction "1_P$1") (pintype "passive"))
    )
    (net (code "87") (name "Net-(R36-1)") (class "Default")
      (node (ref "LED36") (pin "A") (pinfunction "A_A") (pintype "passive"))
      (node (ref "R36") (pin "P$1") (pinfunction "1_P$1") (pintype "passive"))
    )
    (net (code "88") (name "Net-(R37-1)") (class "Default")
      (node (ref "LED37") (pin "A") (pinfunction "A_A") (pintype "passive"))
      (node (ref "R37") (pin "P$1") (pinfunction "1_P$1") (pintype "passive"))
    )
    (net (code "89") (name "Net-(R38-1)") (class "Default")
      (node (ref "LED38") (pin "A") (pinfunction "A_A") (pintype "passive"))
      (node (ref "R38") (pin "P$1") (pinfunction "1_P$1") (pintype "passive"))
    )
    (net (code "90") (name "Net-(R39-1)") (class "Default")
      (node (ref "LED39") (pin "A") (pinfunction "A_A") (pintype "passive"))
      (node (ref "R39") (pin "P$1") (pinfunction "1_P$1") (pintype "passive"))
    )
    (net (code "91") (name "Net-(R40-1)") (class "Default")
      (node (ref "LED40") (pin "A") (pinfunction "A_A") (pintype "passive"))
      (node (ref "R40") (pin "P$1") (pinfunction "1_P$1") (pintype "passive"))
    )
    (net (code "92") (name "Net-(R41-1)") (class "Default")
      (node (ref "LED41") (pin "A") (pinfunction "A_A") (pintype "passive"))
      (node (ref "R41") (pin "P$1") (pinfunction "1_P$1") (pintype "passive"))
    )
    (net (code "93") (name "Net-(R42-1)") (class "Default")
      (node (ref "J15") (pin "P$3") (pinfunction "P$3_P$3") (pintype "bidirectional"))
      (node (ref "R42") (pin "P$1") (pinfunction "1_P$1") (pintype "passive"))
    )
    (net (code "94") (name "Net-(R42-2)") (class "Default")
      (node (ref "R42") (pin "P$2") (pinfunction "2_P$2") (pintype "passive"))
      (node (ref "SW3") (pin "3") (pinfunction "3_3") (pintype "passive"))
    )
    (net (code "95") (name "Net-(R43-1)") (class "Default")
      (node (ref "LED43") (pin "A") (pinfunction "A_A") (pintype "passive"))
      (node (ref "R43") (pin "P$1") (pinfunction "1_P$1") (pintype "passive"))
    )
    (net (code "96") (name "Net-(R44-1)") (class "Default")
      (node (ref "LED44") (pin "A") (pinfunction "A_A") (pintype "passive"))
      (node (ref "R44") (pin "P$1") (pinfunction "1_P$1") (pintype "passive"))
    )
    (net (code "97") (name "Net-(R45-1)") (class "Default")
      (node (ref "LED45") (pin "A") (pinfunction "A_A") (pintype "passive"))
      (node (ref "R45") (pin "P$1") (pinfunction "1_P$1") (pintype "passive"))
    )
    (net (code "98") (name "Net-(R46-1)") (class "Default")
      (node (ref "J15") (pin "P$4") (pinfunction "P$4_P$4") (pintype "bidirectional"))
      (node (ref "R46") (pin "P$1") (pinfunction "1_P$1") (pintype "passive"))
    )
    (net (code "99") (name "Net-(R46-2)") (class "Default")
      (node (ref "R46") (pin "P$2") (pinfunction "2_P$2") (pintype "passive"))
      (node (ref "SW4") (pin "3") (pinfunction "3_3") (pintype "passive"))
    )
    (net (code "100") (name "Net-(R47-1)") (class "Default")
      (node (ref "LED47") (pin "A") (pinfunction "A_A") (pintype "passive"))
      (node (ref "R47") (pin "P$1") (pinfunction "1_P$1") (pintype "passive"))
    )
    (net (code "101") (name "Net-(R48-1)") (class "Default")
      (node (ref "LED48") (pin "A") (pinfunction "A_A") (pintype "passive"))
      (node (ref "R48") (pin "P$1") (pinfunction "1_P$1") (pintype "passive"))
    )
    (net (code "102") (name "Net-(R49-1)") (class "Default")
      (node (ref "LED49") (pin "A") (pinfunction "A_A") (pintype "passive"))
      (node (ref "R49") (pin "P$1") (pinfunction "1_P$1") (pintype "passive"))
    )
    (net (code "103") (name "Net-(R51-1)") (class "Default")
      (node (ref "LED51") (pin "A") (pinfunction "A_A") (pintype "passive"))
      (node (ref "R51") (pin "P$1") (pinfunction "1_P$1") (pintype "passive"))
    )
    (net (code "104") (name "Net-(R52-1)") (class "Default")
      (node (ref "LED52") (pin "A") (pinfunction "A_A") (pintype "passive"))
      (node (ref "R52") (pin "P$1") (pinfunction "1_P$1") (pintype "passive"))
    )
    (net (code "105") (name "Net-(R53-1)") (class "Default")
      (node (ref "LED53") (pin "A") (pinfunction "A_A") (pintype "passive"))
      (node (ref "R53") (pin "P$1") (pinfunction "1_P$1") (pintype "passive"))
    )
    (net (code "106") (name "Net-(R55-1)") (class "Default")
      (node (ref "LED55") (pin "A") (pinfunction "A_A") (pintype "passive"))
      (node (ref "R55") (pin "P$1") (pinfunction "1_P$1") (pintype "passive"))
    )
    (net (code "107") (name "Net-(R56-1)") (class "Default")
      (node (ref "LED56") (pin "A") (pinfunction "A_A") (pintype "passive"))
      (node (ref "R56") (pin "P$1") (pinfunction "1_P$1") (pintype "passive"))
    )
    (net (code "108") (name "Net-(R57-1)") (class "Default")
      (node (ref "LED57") (pin "A") (pinfunction "A_A") (pintype "passive"))
      (node (ref "R57") (pin "P$1") (pinfunction "1_P$1") (pintype "passive"))
    )
    (net (code "109") (name "Net-(R59-1)") (class "Default")
      (node (ref "LED59") (pin "A") (pinfunction "A_A") (pintype "passive"))
      (node (ref "R59") (pin "P$1") (pinfunction "1_P$1") (pintype "passive"))
    )
    (net (code "110") (name "Net-(R60-1)") (class "Default")
      (node (ref "LED60") (pin "A") (pinfunction "A_A") (pintype "passive"))
      (node (ref "R60") (pin "P$1") (pinfunction "1_P$1") (pintype "passive"))
    )
    (net (code "111") (name "Net-(R61-1)") (class "Default")
      (node (ref "LED61") (pin "A") (pinfunction "A_A") (pintype "passive"))
      (node (ref "R61") (pin "P$1") (pinfunction "1_P$1") (pintype "passive"))
    )
    (net (code "112") (name "Net-(R63-1)") (class "Default")
      (node (ref "LED63") (pin "A") (pinfunction "A_A") (pintype "passive"))
      (node (ref "R63") (pin "P$1") (pinfunction "1_P$1") (pintype "passive"))
    )
    (net (code "113") (name "Net-(R64-1)") (class "Default")
      (node (ref "LED64") (pin "A") (pinfunction "A_A") (pintype "passive"))
      (node (ref "R64") (pin "P$1") (pinfunction "1_P$1") (pintype "passive"))
    )
    (net (code "114") (name "Net-(R65-1)") (class "Default")
      (node (ref "LED65") (pin "A") (pinfunction "A_A") (pintype "passive"))
      (node (ref "R65") (pin "P$1") (pinfunction "1_P$1") (pintype "passive"))
    )
    (net (code "115") (name "Net-(R67-1)") (class "Default")
      (node (ref "LED67") (pin "A") (pinfunction "A_A") (pintype "passive"))
      (node (ref "R67") (pin "P$1") (pinfunction "1_P$1") (pintype "passive"))
    )
    (net (code "116") (name "Net-(R68-1)") (class "Default")
      (node (ref "LED68") (pin "A") (pinfunction "A_A") (pintype "passive"))
      (node (ref "R68") (pin "P$1") (pinfunction "1_P$1") (pintype "passive"))
    )
    (net (code "117") (name "Net-(R69-1)") (class "Default")
      (node (ref "LED69") (pin "A") (pinfunction "A_A") (pintype "passive"))
      (node (ref "R69") (pin "P$1") (pinfunction "1_P$1") (pintype "passive"))
    )
    (net (code "118") (name "Net-(R71-1)") (class "Default")
      (node (ref "LED71") (pin "A") (pinfunction "A_A") (pintype "passive"))
      (node (ref "R71") (pin "P$1") (pinfunction "1_P$1") (pintype "passive"))
    )
    (net (code "119") (name "Net-(R72-1)") (class "Default")
      (node (ref "LED72") (pin "A") (pinfunction "A_A") (pintype "passive"))
      (node (ref "R72") (pin "P$1") (pinfunction "1_P$1") (pintype "passive"))
    )
    (net (code "120") (name "Net-(R73-1)") (class "Default")
      (node (ref "LED73") (pin "A") (pinfunction "A_A") (pintype "passive"))
      (node (ref "R73") (pin "P$1") (pinfunction "1_P$1") (pintype "passive"))
    )
    (net (code "121") (name "Net-(R75-1)") (class "Default")
      (node (ref "LED75") (pin "A") (pinfunction "A_A") (pintype "passive"))
      (node (ref "R75") (pin "P$1") (pinfunction "1_P$1") (pintype "passive"))
    )
    (net (code "122") (name "Net-(R76-1)") (class "Default")
      (node (ref "LED76") (pin "A") (pinfunction "A_A") (pintype "passive"))
      (node (ref "R76") (pin "P$1") (pinfunction "1_P$1") (pintype "passive"))
    )
    (net (code "123") (name "Net-(R77-1)") (class "Default")
      (node (ref "LED77") (pin "A") (pinfunction "A_A") (pintype "passive"))
      (node (ref "R77") (pin "P$1") (pinfunction "1_P$1") (pintype "passive"))
    )
    (net (code "124") (name "Net-(R79-1)") (class "Default")
      (node (ref "LED79") (pin "A") (pinfunction "A_A") (pintype "passive"))
      (node (ref "R79") (pin "P$1") (pinfunction "1_P$1") (pintype "passive"))
    )
    (net (code "125") (name "Net-(R80-1)") (class "Default")
      (node (ref "LED80") (pin "A") (pinfunction "A_A") (pintype "passive"))
      (node (ref "R80") (pin "P$1") (pinfunction "1_P$1") (pintype "passive"))
    )
    (net (code "126") (name "Net-(R81-1)") (class "Default")
      (node (ref "LED81") (pin "A") (pinfunction "A_A") (pintype "passive"))
      (node (ref "R81") (pin "P$1") (pinfunction "1_P$1") (pintype "passive"))
    )
    (net (code "127") (name "Net-(R83-1)") (class "Default")
      (node (ref "LED83") (pin "A") (pinfunction "A_A") (pintype "passive"))
      (node (ref "R83") (pin "P$1") (pinfunction "1_P$1") (pintype "passive"))
    )
    (net (code "128") (name "Net-(R84-1)") (class "Default")
      (node (ref "LED84") (pin "A") (pinfunction "A_A") (pintype "passive"))
      (node (ref "R84") (pin "P$1") (pinfunction "1_P$1") (pintype "passive"))
    )
    (net (code "129") (name "Net-(R85-1)") (class "Default")
      (node (ref "LED85") (pin "A") (pinfunction "A_A") (pintype "passive"))
      (node (ref "R85") (pin "P$1") (pinfunction "1_P$1") (pintype "passive"))
    )
    (net (code "130") (name "Net-(R87-1)") (class "Default")
      (node (ref "LED87") (pin "A") (pinfunction "A_A") (pintype "passive"))
      (node (ref "R87") (pin "P$1") (pinfunction "1_P$1") (pintype "passive"))
    )
    (net (code "131") (name "Net-(R88-1)") (class "Default")
      (node (ref "LED88") (pin "A") (pinfunction "A_A") (pintype "passive"))
      (node (ref "R88") (pin "P$1") (pinfunction "1_P$1") (pintype "passive"))
    )
    (net (code "132") (name "Net-(R89-1)") (class "Default")
      (node (ref "LED89") (pin "A") (pinfunction "A_A") (pintype "passive"))
      (node (ref "R89") (pin "P$1") (pinfunction "1_P$1") (pintype "passive"))
    )
    (net (code "133") (name "Net-(R91-1)") (class "Default")
      (node (ref "LED91") (pin "A") (pinfunction "A_A") (pintype "passive"))
      (node (ref "R91") (pin "P$1") (pinfunction "1_P$1") (pintype "passive"))
    )
    (net (code "134") (name "Net-(R92-1)") (class "Default")
      (node (ref "LED92") (pin "A") (pinfunction "A_A") (pintype "passive"))
      (node (ref "R92") (pin "P$1") (pinfunction "1_P$1") (pintype "passive"))
    )
    (net (code "135") (name "Net-(R93-1)") (class "Default")
      (node (ref "LED93") (pin "A") (pinfunction "A_A") (pintype "passive"))
      (node (ref "R93") (pin "P$1") (pinfunction "1_P$1") (pintype "passive"))
    )
    (net (code "136") (name "Net-(R95-1)") (class "Default")
      (node (ref "LED95") (pin "A") (pinfunction "A_A") (pintype "passive"))
      (node (ref "R95") (pin "P$1") (pinfunction "1_P$1") (pintype "passive"))
    )
    (net (code "137") (name "Net-(R97-1)") (class "Default")
      (node (ref "LED97") (pin "A") (pinfunction "A_A") (pintype "passive"))
      (node (ref "R97") (pin "P$1") (pinfunction "1_P$1") (pintype "passive"))
    )
    (net (code "138") (name "Net-(R99-1)") (class "Default")
      (node (ref "LED99") (pin "A") (pinfunction "A_A") (pintype "passive"))
      (node (ref "R99") (pin "P$1") (pinfunction "1_P$1") (pintype "passive"))
    )
    (net (code "139") (name "Net-(RYS1-2)") (class "Default")
      (node (ref "RYS1") (pin "P$2") (pinfunction "2_P$2") (pintype "passive"))
      (node (ref "U1") (pin "1") (pinfunction "B(2)_1") (pintype "input"))
    )
    (net (code "140") (name "Net-(RYS2-2)") (class "Default")
      (node (ref "RYS2") (pin "P$2") (pinfunction "2_P$2") (pintype "passive"))
      (node (ref "U2") (pin "1") (pinfunction "B(2)_1") (pintype "input"))
    )
    (net (code "141") (name "Net-(RYS3-2)") (class "Default")
      (node (ref "RYS3") (pin "P$2") (pinfunction "2_P$2") (pintype "passive"))
      (node (ref "U3") (pin "1") (pinfunction "B(2)_1") (pintype "input"))
    )
    (net (code "142") (name "Net-(RYS4-2)") (class "Default")
      (node (ref "RYS4") (pin "P$2") (pinfunction "2_P$2") (pintype "passive"))
      (node (ref "U4") (pin "1") (pinfunction "B(2)_1") (pintype "input"))
    )
    (net (code "143") (name "Net-(RYS5-2)") (class "Default")
      (node (ref "RYS5") (pin "P$2") (pinfunction "2_P$2") (pintype "passive"))
      (node (ref "U5") (pin "1") (pinfunction "B(2)_1") (pintype "input"))
    )
    (net (code "144") (name "Net-(RYS6-2)") (class "Default")
      (node (ref "RYS6") (pin "P$2") (pinfunction "2_P$2") (pintype "passive"))
      (node (ref "U6") (pin "1") (pinfunction "B(2)_1") (pintype "input"))
    )
    (net (code "145") (name "Net-(RYS7-2)") (class "Default")
      (node (ref "RYS7") (pin "P$2") (pinfunction "2_P$2") (pintype "passive"))
      (node (ref "U7") (pin "1") (pinfunction "B(2)_1") (pintype "input"))
    )
    (net (code "146") (name "Net-(RYS9-2)") (class "Default")
      (node (ref "RYS9") (pin "P$2") (pinfunction "2_P$2") (pintype "passive"))
      (node (ref "U8") (pin "1") (pinfunction "B(2)_1") (pintype "input"))
    )
    (net (code "147") (name "Net-(RYS10-2)") (class "Default")
      (node (ref "RYS10") (pin "P$2") (pinfunction "2_P$2") (pintype "passive"))
      (node (ref "U9") (pin "1") (pinfunction "B(2)_1") (pintype "input"))
    )
    (net (code "148") (name "Net-(RYS11-2)") (class "Default")
      (node (ref "RYS11") (pin "P$2") (pinfunction "2_P$2") (pintype "passive"))
      (node (ref "U10") (pin "1") (pinfunction "B(2)_1") (pintype "input"))
    )
    (net (code "149") (name "Net-(RYS12-2)") (class "Default")
      (node (ref "RYS12") (pin "P$2") (pinfunction "2_P$2") (pintype "passive"))
      (node (ref "U11") (pin "1") (pinfunction "B(2)_1") (pintype "input"))
    )
    (net (code "150") (name "Net-(RYS14-2)") (class "Default")
      (node (ref "RYS14") (pin "P$2") (pinfunction "2_P$2") (pintype "passive"))
      (node (ref "U13") (pin "1") (pinfunction "B(2)_1") (pintype "input"))
    )
    (net (code "151") (name "Net-(RYS15-2)") (class "Default")
      (node (ref "RYS15") (pin "P$2") (pinfunction "2_P$2") (pintype "passive"))
      (node (ref "U14") (pin "1") (pinfunction "B(2)_1") (pintype "input"))
    )
    (net (code "152") (name "Net-(RYS16-2)") (class "Default")
      (node (ref "RYS16") (pin "P$2") (pinfunction "2_P$2") (pintype "passive"))
      (node (ref "U15") (pin "1") (pinfunction "B(2)_1") (pintype "input"))
    )
    (net (code "153") (name "Net-(RYS17-2)") (class "Default")
      (node (ref "RYS17") (pin "P$2") (pinfunction "2_P$2") (pintype "passive"))
      (node (ref "U16") (pin "1") (pinfunction "B(2)_1") (pintype "input"))
    )
    (net (code "154") (name "Net-(RYS18-2)") (class "Default")
      (node (ref "RYS18") (pin "P$2") (pinfunction "2_P$2") (pintype "passive"))
      (node (ref "U17") (pin "1") (pinfunction "B(2)_1") (pintype "input"))
    )
    (net (code "155") (name "Net-(RYS19-2)") (class "Default")
      (node (ref "RYS19") (pin "P$2") (pinfunction "2_P$2") (pintype "passive"))
      (node (ref "U18") (pin "1") (pinfunction "B(2)_1") (pintype "input"))
    )
    (net (code "156") (name "Net-(RYS20-2)") (class "Default")
      (node (ref "RYS20") (pin "P$2") (pinfunction "2_P$2") (pintype "passive"))
      (node (ref "U20") (pin "1") (pinfunction "B(2)_1") (pintype "input"))
    )
    (net (code "157") (name "Net-(RYS22-2)") (class "Default")
      (node (ref "RYS22") (pin "P$2") (pinfunction "2_P$2") (pintype "passive"))
      (node (ref "U22") (pin "1") (pinfunction "B(2)_1") (pintype "input"))
    )
    (net (code "158") (name "Net-(RYS23-2)") (class "Default")
      (node (ref "RYS23") (pin "P$2") (pinfunction "2_P$2") (pintype "passive"))
      (node (ref "U23") (pin "1") (pinfunction "B(2)_1") (pintype "input"))
    )
    (net (code "159") (name "Net-(RYS24-2)") (class "Default")
      (node (ref "RYS24") (pin "P$2") (pinfunction "2_P$2") (pintype "passive"))
      (node (ref "U24") (pin "1") (pinfunction "B(2)_1") (pintype "input"))
    )
    (net (code "160") (name "Net-(RYS26-2)") (class "Default")
      (node (ref "RYS26") (pin "P$2") (pinfunction "2_P$2") (pintype "passive"))
      (node (ref "U26") (pin "1") (pinfunction "B(2)_1") (pintype "input"))
    )
    (net (code "161") (name "Net-(RYS27-2)") (class "Default")
      (node (ref "RYS27") (pin "P$2") (pinfunction "2_P$2") (pintype "passive"))
      (node (ref "U27") (pin "1") (pinfunction "B(2)_1") (pintype "input"))
    )
    (net (code "162") (name "Net-(RYS28-2)") (class "Default")
      (node (ref "RYS28") (pin "P$2") (pinfunction "2_P$2") (pintype "passive"))
      (node (ref "U28") (pin "1") (pinfunction "B(2)_1") (pintype "input"))
    )
    (net (code "163") (name "Net-(RYS30-2)") (class "Default")
      (node (ref "RYS30") (pin "P$2") (pinfunction "2_P$2") (pintype "passive"))
      (node (ref "U30") (pin "1") (pinfunction "B(2)_1") (pintype "input"))
    )
    (net (code "164") (name "Net-(RYS31-2)") (class "Default")
      (node (ref "RYS31") (pin "P$2") (pinfunction "2_P$2") (pintype "passive"))
      (node (ref "U31") (pin "1") (pinfunction "B(2)_1") (pintype "input"))
    )
    (net (code "165") (name "Net-(RYS32-2)") (class "Default")
      (node (ref "RYS32") (pin "P$2") (pinfunction "2_P$2") (pintype "passive"))
      (node (ref "U32") (pin "1") (pinfunction "B(2)_1") (pintype "input"))
    )
    (net (code "166") (name "Net-(RYS34-2)") (class "Default")
      (node (ref "RYS34") (pin "P$2") (pinfunction "2_P$2") (pintype "passive"))
      (node (ref "U34") (pin "1") (pinfunction "B(2)_1") (pintype "input"))
    )
    (net (code "167") (name "Net-(RYS35-2)") (class "Default")
      (node (ref "RYS35") (pin "P$2") (pinfunction "2_P$2") (pintype "passive"))
      (node (ref "U35") (pin "1") (pinfunction "B(2)_1") (pintype "input"))
    )
    (net (code "168") (name "Net-(RYS36-2)") (class "Default")
      (node (ref "RYS36") (pin "P$2") (pinfunction "2_P$2") (pintype "passive"))
      (node (ref "U36") (pin "1") (pinfunction "B(2)_1") (pintype "input"))
    )
    (net (code "169") (name "Net-(RYS38-2)") (class "Default")
      (node (ref "RYS38") (pin "P$2") (pinfunction "2_P$2") (pintype "passive"))
      (node (ref "U38") (pin "1") (pinfunction "B(2)_1") (pintype "input"))
    )
    (net (code "170") (name "Net-(RYS39-2)") (class "Default")
      (node (ref "RYS39") (pin "P$2") (pinfunction "2_P$2") (pintype "passive"))
      (node (ref "U39") (pin "1") (pinfunction "B(2)_1") (pintype "input"))
    )
    (net (code "171") (name "Net-(RYS40-2)") (class "Default")
      (node (ref "RYS40") (pin "P$2") (pinfunction "2_P$2") (pintype "passive"))
      (node (ref "U40") (pin "1") (pinfunction "B(2)_1") (pintype "input"))
    )
    (net (code "172") (name "Net-(RYS42-2)") (class "Default")
      (node (ref "RYS42") (pin "P$2") (pinfunction "2_P$2") (pintype "passive"))
      (node (ref "U42") (pin "1") (pinfunction "B(2)_1") (pintype "input"))
    )
    (net (code "173") (name "Net-(RYS43-2)") (class "Default")
      (node (ref "RYS43") (pin "P$2") (pinfunction "2_P$2") (pintype "passive"))
      (node (ref "U43") (pin "1") (pinfunction "B(2)_1") (pintype "input"))
    )
    (net (code "174") (name "Net-(RYS44-2)") (class "Default")
      (node (ref "RYS44") (pin "P$2") (pinfunction "2_P$2") (pintype "passive"))
      (node (ref "U44") (pin "1") (pinfunction "B(2)_1") (pintype "input"))
    )
    (net (code "175") (name "Net-(RYS46-2)") (class "Default")
      (node (ref "RYS46") (pin "P$2") (pinfunction "2_P$2") (pintype "passive"))
      (node (ref "U46") (pin "1") (pinfunction "B(2)_1") (pintype "input"))
    )
    (net (code "176") (name "Net-(RYS47-2)") (class "Default")
      (node (ref "RYS47") (pin "P$2") (pinfunction "2_P$2") (pintype "passive"))
      (node (ref "U47") (pin "1") (pinfunction "B(2)_1") (pintype "input"))
    )
    (net (code "177") (name "Net-(RYS48-2)") (class "Default")
      (node (ref "RYS48") (pin "P$2") (pinfunction "2_P$2") (pintype "passive"))
      (node (ref "U48") (pin "1") (pinfunction "B(2)_1") (pintype "input"))
    )
    (net (code "178") (name "Net-(RYS50-2)") (class "Default")
      (node (ref "RYS50") (pin "P$2") (pinfunction "2_P$2") (pintype "passive"))
      (node (ref "U50") (pin "1") (pinfunction "B(2)_1") (pintype "input"))
    )
    (net (code "179") (name "Net-(RYS51-2)") (class "Default")
      (node (ref "RYS51") (pin "P$2") (pinfunction "2_P$2") (pintype "passive"))
      (node (ref "U51") (pin "1") (pinfunction "B(2)_1") (pintype "input"))
    )
    (net (code "180") (name "Net-(RYS52-2)") (class "Default")
      (node (ref "RYS52") (pin "P$2") (pinfunction "2_P$2") (pintype "passive"))
      (node (ref "U52") (pin "1") (pinfunction "B(2)_1") (pintype "input"))
    )
    (net (code "181") (name "Net-(RYS54-2)") (class "Default")
      (node (ref "RYS54") (pin "P$2") (pinfunction "2_P$2") (pintype "passive"))
      (node (ref "U54") (pin "1") (pinfunction "B(2)_1") (pintype "input"))
    )
    (net (code "182") (name "Net-(RYS55-2)") (class "Default")
      (node (ref "RYS55") (pin "P$2") (pinfunction "2_P$2") (pintype "passive"))
      (node (ref "U55") (pin "1") (pinfunction "B(2)_1") (pintype "input"))
    )
    (net (code "183") (name "Net-(RYS56-2)") (class "Default")
      (node (ref "RYS56") (pin "P$2") (pinfunction "2_P$2") (pintype "passive"))
      (node (ref "U56") (pin "1") (pinfunction "B(2)_1") (pintype "input"))
    )
    (net (code "184") (name "Net-(RYS58-2)") (class "Default")
      (node (ref "RYS58") (pin "P$2") (pinfunction "2_P$2") (pintype "passive"))
      (node (ref "U58") (pin "1") (pinfunction "B(2)_1") (pintype "input"))
    )
    (net (code "185") (name "Net-(RYS59-2)") (class "Default")
      (node (ref "RYS59") (pin "P$2") (pinfunction "2_P$2") (pintype "passive"))
      (node (ref "U59") (pin "1") (pinfunction "B(2)_1") (pintype "input"))
    )
    (net (code "186") (name "Net-(RYS60-2)") (class "Default")
      (node (ref "RYS60") (pin "P$2") (pinfunction "2_P$2") (pintype "passive"))
      (node (ref "U60") (pin "1") (pinfunction "B(2)_1") (pintype "input"))
    )
    (net (code "187") (name "Net-(RYS62-2)") (class "Default")
      (node (ref "RYS62") (pin "P$2") (pinfunction "2_P$2") (pintype "passive"))
      (node (ref "U62") (pin "1") (pinfunction "B(2)_1") (pintype "input"))
    )
    (net (code "188") (name "Net-(RYS63-2)") (class "Default")
      (node (ref "RYS63") (pin "P$2") (pinfunction "2_P$2") (pintype "passive"))
      (node (ref "U63") (pin "1") (pinfunction "B(2)_1") (pintype "input"))
    )
    (net (code "189") (name "Net-(RYS64-2)") (class "Default")
      (node (ref "RYS64") (pin "P$2") (pinfunction "2_P$2") (pintype "passive"))
      (node (ref "U64") (pin "1") (pinfunction "B(2)_1") (pintype "input"))
    )
    (net (code "190") (name "Net-(RYS66-2)") (class "Default")
      (node (ref "RYS66") (pin "P$2") (pinfunction "2_P$2") (pintype "passive"))
      (node (ref "U66") (pin "1") (pinfunction "B(2)_1") (pintype "input"))
    )
    (net (code "191") (name "Net-(RYS67-2)") (class "Default")
      (node (ref "RYS67") (pin "P$2") (pinfunction "2_P$2") (pintype "passive"))
      (node (ref "U67") (pin "1") (pinfunction "B(2)_1") (pintype "input"))
    )
    (net (code "192") (name "Net-(RYS68-2)") (class "Default")
      (node (ref "RYS68") (pin "P$2") (pinfunction "2_P$2") (pintype "passive"))
      (node (ref "U68") (pin "1") (pinfunction "B(2)_1") (pintype "input"))
    )
    (net (code "193") (name "Net-(RYS70-2)") (class "Default")
      (node (ref "RYS70") (pin "P$2") (pinfunction "2_P$2") (pintype "passive"))
      (node (ref "U70") (pin "1") (pinfunction "B(2)_1") (pintype "input"))
    )
    (net (code "194") (name "Net-(RYS71-2)") (class "Default")
      (node (ref "RYS71") (pin "P$2") (pinfunction "2_P$2") (pintype "passive"))
      (node (ref "U71") (pin "1") (pinfunction "B(2)_1") (pintype "input"))
    )
    (net (code "195") (name "Net-(RYS72-2)") (class "Default")
      (node (ref "RYS72") (pin "P$2") (pinfunction "2_P$2") (pintype "passive"))
      (node (ref "U72") (pin "1") (pinfunction "B(2)_1") (pintype "input"))
    )
    (net (code "196") (name "Net-(RYS74-2)") (class "Default")
      (node (ref "RYS74") (pin "P$2") (pinfunction "2_P$2") (pintype "passive"))
      (node (ref "U74") (pin "1") (pinfunction "B(2)_1") (pintype "input"))
    )
    (net (code "197") (name "Net-(RYS76-2)") (class "Default")
      (node (ref "RYS76") (pin "P$2") (pinfunction "2_P$2") (pintype "passive"))
      (node (ref "U76") (pin "1") (pinfunction "B(2)_1") (pintype "input"))
    )
    (net (code "198") (name "Net-(RYS78-2)") (class "Default")
      (node (ref "RYS78") (pin "P$2") (pinfunction "2_P$2") (pintype "passive"))
      (node (ref "U78") (pin "1") (pinfunction "B(2)_1") (pintype "input"))
    )
    (net (code "199") (name "Net-(U1-C(3))") (class "Default")
      (node (ref "LED23") (pin "C") (pinfunction "C_C") (pintype "passive"))
      (node (ref "U1") (pin "3") (pinfunction "C(3)_3") (pintype "input"))
    )
    (net (code "200") (name "Net-(U2-C(3))") (class "Default")
      (node (ref "LED24") (pin "C") (pinfunction "C_C") (pintype "passive"))
      (node (ref "U2") (pin "3") (pinfunction "C(3)_3") (pintype "input"))
    )
    (net (code "201") (name "Net-(U3-C(3))") (class "Default")
      (node (ref "LED25") (pin "C") (pinfunction "C_C") (pintype "passive"))
      (node (ref "U3") (pin "3") (pinfunction "C(3)_3") (pintype "input"))
    )
    (net (code "202") (name "Net-(U4-C(3))") (class "Default")
      (node (ref "LED26") (pin "C") (pinfunction "C_C") (pintype "passive"))
      (node (ref "U4") (pin "3") (pinfunction "C(3)_3") (pintype "input"))
    )
    (net (code "203") (name "Net-(U5-C(3))") (class "Default")
      (node (ref "LED27") (pin "C") (pinfunction "C_C") (pintype "passive"))
      (node (ref "U5") (pin "3") (pinfunction "C(3)_3") (pintype "input"))
    )
    (net (code "204") (name "Net-(U6-C(3))") (class "Default")
      (node (ref "LED28") (pin "C") (pinfunction "C_C") (pintype "passive"))
      (node (ref "U6") (pin "3") (pinfunction "C(3)_3") (pintype "input"))
    )
    (net (code "205") (name "Net-(U7-C(3))") (class "Default")
      (node (ref "LED29") (pin "C") (pinfunction "C_C") (pintype "passive"))
      (node (ref "U7") (pin "3") (pinfunction "C(3)_3") (pintype "input"))
    )
    (net (code "206") (name "Net-(U8-C(3))") (class "Default")
      (node (ref "LED30") (pin "C") (pinfunction "C_C") (pintype "passive"))
      (node (ref "U8") (pin "3") (pinfunction "C(3)_3") (pintype "input"))
    )
    (net (code "207") (name "Net-(U9-C(3))") (class "Default")
      (node (ref "LED31") (pin "C") (pinfunction "C_C") (pintype "passive"))
      (node (ref "U9") (pin "3") (pinfunction "C(3)_3") (pintype "input"))
    )
    (net (code "208") (name "Net-(U10-C(3))") (class "Default")
      (node (ref "LED32") (pin "C") (pinfunction "C_C") (pintype "passive"))
      (node (ref "U10") (pin "3") (pinfunction "C(3)_3") (pintype "input"))
    )
    (net (code "209") (name "Net-(U11-C(3))") (class "Default")
      (node (ref "LED33") (pin "C") (pinfunction "C_C") (pintype "passive"))
      (node (ref "U11") (pin "3") (pinfunction "C(3)_3") (pintype "input"))
    )
    (net (code "210") (name "Net-(U13-C(3))") (class "Default")
      (node (ref "LED35") (pin "C") (pinfunction "C_C") (pintype "passive"))
      (node (ref "U13") (pin "3") (pinfunction "C(3)_3") (pintype "input"))
    )
    (net (code "211") (name "Net-(U14-C(3))") (class "Default")
      (node (ref "LED36") (pin "C") (pinfunction "C_C") (pintype "passive"))
      (node (ref "U14") (pin "3") (pinfunction "C(3)_3") (pintype "input"))
    )
    (net (code "212") (name "Net-(U15-C(3))") (class "Default")
      (node (ref "LED37") (pin "C") (pinfunction "C_C") (pintype "passive"))
      (node (ref "U15") (pin "3") (pinfunction "C(3)_3") (pintype "input"))
    )
    (net (code "213") (name "Net-(U16-C(3))") (class "Default")
      (node (ref "LED38") (pin "C") (pinfunction "C_C") (pintype "passive"))
      (node (ref "U16") (pin "3") (pinfunction "C(3)_3") (pintype "input"))
    )
    (net (code "214") (name "Net-(U17-C(3))") (class "Default")
      (node (ref "LED39") (pin "C") (pinfunction "C_C") (pintype "passive"))
      (node (ref "U17") (pin "3") (pinfunction "C(3)_3") (pintype "input"))
    )
    (net (code "215") (name "Net-(U18-C(3))") (class "Default")
      (node (ref "LED40") (pin "C") (pinfunction "C_C") (pintype "passive"))
      (node (ref "U18") (pin "3") (pinfunction "C(3)_3") (pintype "input"))
    )
    (net (code "216") (name "Net-(U20-C(3))") (class "Default")
      (node (ref "LED41") (pin "C") (pinfunction "C_C") (pintype "passive"))
      (node (ref "U20") (pin "3") (pinfunction "C(3)_3") (pintype "input"))
    )
    (net (code "217") (name "Net-(U22-C(3))") (class "Default")
      (node (ref "LED43") (pin "C") (pinfunction "C_C") (pintype "passive"))
      (node (ref "U22") (pin "3") (pinfunction "C(3)_3") (pintype "input"))
    )
    (net (code "218") (name "Net-(U23-C(3))") (class "Default")
      (node (ref "LED44") (pin "C") (pinfunction "C_C") (pintype "passive"))
      (node (ref "U23") (pin "3") (pinfunction "C(3)_3") (pintype "input"))
    )
    (net (code "219") (name "Net-(U24-C(3))") (class "Default")
      (node (ref "LED45") (pin "C") (pinfunction "C_C") (pintype "passive"))
      (node (ref "U24") (pin "3") (pinfunction "C(3)_3") (pintype "input"))
    )
    (net (code "220") (name "Net-(U26-C(3))") (class "Default")
      (node (ref "LED47") (pin "C") (pinfunction "C_C") (pintype "passive"))
      (node (ref "U26") (pin "3") (pinfunction "C(3)_3") (pintype "input"))
    )
    (net (code "221") (name "Net-(U27-C(3))") (class "Default")
      (node (ref "LED48") (pin "C") (pinfunction "C_C") (pintype "passive"))
      (node (ref "U27") (pin "3") (pinfunction "C(3)_3") (pintype "input"))
    )
    (net (code "222") (name "Net-(U28-C(3))") (class "Default")
      (node (ref "LED49") (pin "C") (pinfunction "C_C") (pintype "passive"))
      (node (ref "U28") (pin "3") (pinfunction "C(3)_3") (pintype "input"))
    )
    (net (code "223") (name "Net-(U30-C(3))") (class "Default")
      (node (ref "LED51") (pin "C") (pinfunction "C_C") (pintype "passive"))
      (node (ref "U30") (pin "3") (pinfunction "C(3)_3") (pintype "input"))
    )
    (net (code "224") (name "Net-(U31-C(3))") (class "Default")
      (node (ref "LED52") (pin "C") (pinfunction "C_C") (pintype "passive"))
      (node (ref "U31") (pin "3") (pinfunction "C(3)_3") (pintype "input"))
    )
    (net (code "225") (name "Net-(U32-C(3))") (class "Default")
      (node (ref "LED53") (pin "C") (pinfunction "C_C") (pintype "passive"))
      (node (ref "U32") (pin "3") (pinfunction "C(3)_3") (pintype "input"))
    )
    (net (code "226") (name "Net-(U34-C(3))") (class "Default")
      (node (ref "LED55") (pin "C") (pinfunction "C_C") (pintype "passive"))
      (node (ref "U34") (pin "3") (pinfunction "C(3)_3") (pintype "input"))
    )
    (net (code "227") (name "Net-(U35-C(3))") (class "Default")
      (node (ref "LED56") (pin "C") (pinfunction "C_C") (pintype "passive"))
      (node (ref "U35") (pin "3") (pinfunction "C(3)_3") (pintype "input"))
    )
    (net (code "228") (name "Net-(U36-C(3))") (class "Default")
      (node (ref "LED57") (pin "C") (pinfunction "C_C") (pintype "passive"))
      (node (ref "U36") (pin "3") (pinfunction "C(3)_3") (pintype "input"))
    )
    (net (code "229") (name "Net-(U38-C(3))") (class "Default")
      (node (ref "LED59") (pin "C") (pinfunction "C_C") (pintype "passive"))
      (node (ref "U38") (pin "3") (pinfunction "C(3)_3") (pintype "input"))
    )
    (net (code "230") (name "Net-(U39-C(3))") (class "Default")
      (node (ref "LED60") (pin "C") (pinfunction "C_C") (pintype "passive"))
      (node (ref "U39") (pin "3") (pinfunction "C(3)_3") (pintype "input"))
    )
    (net (code "231") (name "Net-(U40-C(3))") (class "Default")
      (node (ref "LED61") (pin "C") (pinfunction "C_C") (pintype "passive"))
      (node (ref "U40") (pin "3") (pinfunction "C(3)_3") (pintype "input"))
    )
    (net (code "232") (name "Net-(U42-C(3))") (class "Default")
      (node (ref "LED63") (pin "C") (pinfunction "C_C") (pintype "passive"))
      (node (ref "U42") (pin "3") (pinfunction "C(3)_3") (pintype "input"))
    )
    (net (code "233") (name "Net-(U43-C(3))") (class "Default")
      (node (ref "LED64") (pin "C") (pinfunction "C_C") (pintype "passive"))
      (node (ref "U43") (pin "3") (pinfunction "C(3)_3") (pintype "input"))
    )
    (net (code "234") (name "Net-(U44-C(3))") (class "Default")
      (node (ref "LED65") (pin "C") (pinfunction "C_C") (pintype "passive"))
      (node (ref "U44") (pin "3") (pinfunction "C(3)_3") (pintype "input"))
    )
    (net (code "235") (name "Net-(U46-C(3))") (class "Default")
      (node (ref "LED67") (pin "C") (pinfunction "C_C") (pintype "passive"))
      (node (ref "U46") (pin "3") (pinfunction "C(3)_3") (pintype "input"))
    )
    (net (code "236") (name "Net-(U47-C(3))") (class "Default")
      (node (ref "LED68") (pin "C") (pinfunction "C_C") (pintype "passive"))
      (node (ref "U47") (pin "3") (pinfunction "C(3)_3") (pintype "input"))
    )
    (net (code "237") (name "Net-(U48-C(3))") (class "Default")
      (node (ref "LED69") (pin "C") (pinfunction "C_C") (pintype "passive"))
      (node (ref "U48") (pin "3") (pinfunction "C(3)_3") (pintype "input"))
    )
    (net (code "238") (name "Net-(U50-C(3))") (class "Default")
      (node (ref "LED71") (pin "C") (pinfunction "C_C") (pintype "passive"))
      (node (ref "U50") (pin "3") (pinfunction "C(3)_3") (pintype "input"))
    )
    (net (code "239") (name "Net-(U51-C(3))") (class "Default")
      (node (ref "LED72") (pin "C") (pinfunction "C_C") (pintype "passive"))
      (node (ref "U51") (pin "3") (pinfunction "C(3)_3") (pintype "input"))
    )
    (net (code "240") (name "Net-(U52-C(3))") (class "Default")
      (node (ref "LED73") (pin "C") (pinfunction "C_C") (pintype "passive"))
      (node (ref "U52") (pin "3") (pinfunction "C(3)_3") (pintype "input"))
    )
    (net (code "241") (name "Net-(U54-C(3))") (class "Default")
      (node (ref "LED75") (pin "C") (pinfunction "C_C") (pintype "passive"))
      (node (ref "U54") (pin "3") (pinfunction "C(3)_3") (pintype "input"))
    )
    (net (code "242") (name "Net-(U55-C(3))") (class "Default")
      (node (ref "LED76") (pin "C") (pinfunction "C_C") (pintype "passive"))
      (node (ref "U55") (pin "3") (pinfunction "C(3)_3") (pintype "input"))
    )
    (net (code "243") (name "Net-(U56-C(3))") (class "Default")
      (node (ref "LED77") (pin "C") (pinfunction "C_C") (pintype "passive"))
      (node (ref "U56") (pin "3") (pinfunction "C(3)_3") (pintype "input"))
    )
    (net (code "244") (name "Net-(U58-C(3))") (class "Default")
      (node (ref "LED79") (pin "C") (pinfunction "C_C") (pintype "passive"))
      (node (ref "U58") (pin "3") (pinfunction "C(3)_3") (pintype "input"))
    )
    (net (code "245") (name "Net-(U59-C(3))") (class "Default")
      (node (ref "LED80") (pin "C") (pinfunction "C_C") (pintype "passive"))
      (node (ref "U59") (pin "3") (pinfunction "C(3)_3") (pintype "input"))
    )
    (net (code "246") (name "Net-(U60-C(3))") (class "Default")
      (node (ref "LED81") (pin "C") (pinfunction "C_C") (pintype "passive"))
      (node (ref "U60") (pin "3") (pinfunction "C(3)_3") (pintype "input"))
    )
    (net (code "247") (name "Net-(U62-C(3))") (class "Default")
      (node (ref "LED83") (pin "C") (pinfunction "C_C") (pintype "passive"))
      (node (ref "U62") (pin "3") (pinfunction "C(3)_3") (pintype "input"))
    )
    (net (code "248") (name "Net-(U63-C(3))") (class "Default")
      (node (ref "LED84") (pin "C") (pinfunction "C_C") (pintype "passive"))
      (node (ref "U63") (pin "3") (pinfunction "C(3)_3") (pintype "input"))
    )
    (net (code "249") (name "Net-(U64-C(3))") (class "Default")
      (node (ref "LED85") (pin "C") (pinfunction "C_C") (pintype "passive"))
      (node (ref "U64") (pin "3") (pinfunction "C(3)_3") (pintype "input"))
    )
    (net (code "250") (name "Net-(U66-C(3))") (class "Default")
      (node (ref "LED87") (pin "C") (pinfunction "C_C") (pintype "passive"))
      (node (ref "U66") (pin "3") (pinfunction "C(3)_3") (pintype "input"))
    )
    (net (code "251") (name "Net-(U67-C(3))") (class "Default")
      (node (ref "LED88") (pin "C") (pinfunction "C_C") (pintype "passive"))
      (node (ref "U67") (pin "3") (pinfunction "C(3)_3") (pintype "input"))
    )
    (net (code "252") (name "Net-(U68-C(3))") (class "Default")
      (node (ref "LED89") (pin "C") (pinfunction "C_C") (pintype "passive"))
      (node (ref "U68") (pin "3") (pinfunction "C(3)_3") (pintype "input"))
    )
    (net (code "253") (name "Net-(U70-C(3))") (class "Default")
      (node (ref "LED91") (pin "C") (pinfunction "C_C") (pintype "passive"))
      (node (ref "U70") (pin "3") (pinfunction "C(3)_3") (pintype "input"))
    )
    (net (code "254") (name "Net-(U71-C(3))") (class "Default")
      (node (ref "LED92") (pin "C") (pinfunction "C_C") (pintype "passive"))
      (node (ref "U71") (pin "3") (pinfunction "C(3)_3") (pintype "input"))
    )
    (net (code "255") (name "Net-(U72-C(3))") (class "Default")
      (node (ref "LED93") (pin "C") (pinfunction "C_C") (pintype "passive"))
      (node (ref "U72") (pin "3") (pinfunction "C(3)_3") (pintype "input"))
    )
    (net (code "256") (name "Net-(U74-C(3))") (class "Default")
      (node (ref "LED95") (pin "C") (pinfunction "C_C") (pintype "passive"))
      (node (ref "U74") (pin "3") (pinfunction "C(3)_3") (pintype "input"))
    )
    (net (code "257") (name "Net-(U76-C(3))") (class "Default")
      (node (ref "LED97") (pin "C") (pinfunction "C_C") (pintype "passive"))
      (node (ref "U76") (pin "3") (pinfunction "C(3)_3") (pintype "input"))
    )
    (net (code "258") (name "Net-(U78-C(3))") (class "Default")
      (node (ref "LED99") (pin "C") (pinfunction "C_C") (pintype "passive"))
      (node (ref "U78") (pin "3") (pinfunction "C(3)_3") (pintype "input"))
    )
    (net (code "259") (name "P1_02") (class "Default")
      (node (ref "J10") (pin "P$7") (pinfunction "P$7_P$7") (pintype "bidirectional"))
      (node (ref "RYS46") (pin "P$1") (pinfunction "1_P$1") (pintype "passive"))
    )
    (net (code "260") (name "P1_03") (class "Default")
      (node (ref "J10") (pin "P$8") (pinfunction "P$8_P$8") (pintype "bidirectional"))
      (node (ref "RYS5") (pin "P$1") (pinfunction "1_P$1") (pintype "passive"))
    )
    (net (code "261") (name "P1_06") (class "Default")
      (node (ref "J10") (pin "P$11") (pinfunction "P$11_P$11") (pintype "bidirectional"))
      (node (ref "RYS50") (pin "P$1") (pinfunction "1_P$1") (pintype "passive"))
    )
    (net (code "262") (name "P1_07") (class "Default")
      (node (ref "J10") (pin "P$12") (pinfunction "P$12_P$12") (pintype "bidirectional"))
      (node (ref "RYS10") (pin "P$1") (pinfunction "1_P$1") (pintype "passive"))
    )
    (net (code "263") (name "P1_11") (class "Default")
      (node (ref "J10") (pin "P$38") (pinfunction "P$38_P$38") (pintype "bidirectional"))
      (node (ref "RYS36") (pin "P$1") (pinfunction "1_P$1") (pintype "passive"))
    )
    (net (code "264") (name "P1_12") (class "Default")
      (node (ref "J10") (pin "P$37") (pinfunction "P$37_P$37") (pintype "bidirectional"))
      (node (ref "RYS76") (pin "P$1") (pinfunction "1_P$1") (pintype "passive"))
    )
    (net (code "265") (name "P1_13") (class "Default")
      (node (ref "J10") (pin "P$36") (pinfunction "P$36_P$36") (pintype "bidirectional"))
      (node (ref "RYS34") (pin "P$1") (pinfunction "1_P$1") (pintype "passive"))
    )
    (net (code "266") (name "P1_14") (class "Default")
      (node (ref "J10") (pin "P$35") (pinfunction "P$35_P$35") (pintype "bidirectional"))
      (node (ref "RYS74") (pin "P$1") (pinfunction "1_P$1") (pintype "passive"))
    )
    (net (code "267") (name "P1_15") (class "Default")
      (node (ref "J10") (pin "P$34") (pinfunction "P$34_P$34") (pintype "bidirectional"))
      (node (ref "RYS32") (pin "P$1") (pinfunction "1_P$1") (pintype "passive"))
    )
    (net (code "268") (name "P6_00") (class "Default")
      (node (ref "J10") (pin "P$13") (pinfunction "P$13_P$13") (pintype "bidirectional"))
      (node (ref "RYS52") (pin "P$1") (pinfunction "1_P$1") (pintype "passive"))
    )
    (net (code "269") (name "P6_01") (class "Default")
      (node (ref "J10") (pin "P$14") (pinfunction "P$14_P$14") (pintype "bidirectional"))
      (node (ref "RYS12") (pin "P$1") (pinfunction "1_P$1") (pintype "passive"))
    )
    (net (code "270") (name "P6_02") (class "Default")
      (node (ref "J10") (pin "P$15") (pinfunction "P$15_P$15") (pintype "bidirectional"))
      (node (ref "RYS54") (pin "P$1") (pinfunction "1_P$1") (pintype "passive"))
    )
    (net (code "271") (name "P6_03") (class "Default")
      (node (ref "J10") (pin "P$16") (pinfunction "P$16_P$16") (pintype "bidirectional"))
      (node (ref "RYS14") (pin "P$1") (pinfunction "1_P$1") (pintype "passive"))
    )
    (net (code "272") (name "P6_04") (class "Default")
      (node (ref "J10") (pin "P$17") (pinfunction "P$17_P$17") (pintype "bidirectional"))
      (node (ref "RYS56") (pin "P$1") (pinfunction "1_P$1") (pintype "passive"))
    )
    (net (code "273") (name "P6_05") (class "Default")
      (node (ref "J10") (pin "P$18") (pinfunction "P$18_P$18") (pintype "bidirectional"))
      (node (ref "RYS16") (pin "P$1") (pinfunction "1_P$1") (pintype "passive"))
    )
    (net (code "274") (name "P6_06") (class "Default")
      (node (ref "J10") (pin "P$19") (pinfunction "P$19_P$19") (pintype "bidirectional"))
      (node (ref "RYS58") (pin "P$1") (pinfunction "1_P$1") (pintype "passive"))
    )
    (net (code "275") (name "P6_07") (class "Default")
      (node (ref "J10") (pin "P$20") (pinfunction "P$20_P$20") (pintype "bidirectional"))
      (node (ref "RYS18") (pin "P$1") (pinfunction "1_P$1") (pintype "passive"))
    )
    (net (code "276") (name "P6_08") (class "Default")
      (node (ref "J10") (pin "P$33") (pinfunction "P$33_P$33") (pintype "bidirectional"))
      (node (ref "RYS72") (pin "P$1") (pinfunction "1_P$1") (pintype "passive"))
    )
    (net (code "277") (name "P6_09") (class "Default")
      (node (ref "J10") (pin "P$32") (pinfunction "P$32_P$32") (pintype "bidirectional"))
      (node (ref "RYS30") (pin "P$1") (pinfunction "1_P$1") (pintype "passive"))
    )
    (net (code "278") (name "P6_10") (class "Default")
      (node (ref "J10") (pin "P$31") (pinfunction "P$31_P$31") (pintype "bidirectional"))
      (node (ref "RYS70") (pin "P$1") (pinfunction "1_P$1") (pintype "passive"))
    )
    (net (code "279") (name "P6_11") (class "Default")
      (node (ref "J10") (pin "P$30") (pinfunction "P$30_P$30") (pintype "bidirectional"))
      (node (ref "RYS28") (pin "P$1") (pinfunction "1_P$1") (pintype "passive"))
    )
    (net (code "280") (name "P6_12") (class "Default")
      (node (ref "J10") (pin "P$29") (pinfunction "P$29_P$29") (pintype "bidirectional"))
      (node (ref "RYS68") (pin "P$1") (pinfunction "1_P$1") (pintype "passive"))
    )
    (net (code "281") (name "P6_13") (class "Default")
      (node (ref "J10") (pin "P$28") (pinfunction "P$28_P$28") (pintype "bidirectional"))
      (node (ref "RYS26") (pin "P$1") (pinfunction "1_P$1") (pintype "passive"))
    )
    (net (code "282") (name "P6_14") (class "Default")
      (node (ref "J10") (pin "P$27") (pinfunction "P$27_P$27") (pintype "bidirectional"))
      (node (ref "RYS66") (pin "P$1") (pinfunction "1_P$1") (pintype "passive"))
    )
    (net (code "283") (name "P6_15") (class "Default")
      (node (ref "J10") (pin "P$26") (pinfunction "P$26_P$26") (pintype "bidirectional"))
      (node (ref "RYS24") (pin "P$1") (pinfunction "1_P$1") (pintype "passive"))
    )
    (net (code "284") (name "P8_00") (class "Default")
      (node (ref "J10") (pin "P$4") (pinfunction "P$4_P$4") (pintype "bidirectional"))
      (node (ref "RYS2") (pin "P$1") (pinfunction "1_P$1") (pintype "passive"))
    )
    (net (code "285") (name "P8_01") (class "Default")
      (node (ref "J10") (pin "P$3") (pinfunction "P$3_P$3") (pintype "bidirectional"))
      (node (ref "RYS42") (pin "P$1") (pinfunction "1_P$1") (pintype "passive"))
    )
    (net (code "286") (name "P8_02") (class "Default")
      (node (ref "J10") (pin "P$2") (pinfunction "P$2_P$2") (pintype "bidirectional"))
      (node (ref "RYS1") (pin "P$1") (pinfunction "1_P$1") (pintype "passive"))
    )
    (net (code "287") (name "PA_00") (class "Default")
      (node (ref "J10") (pin "P$21") (pinfunction "P$21_P$21") (pintype "bidirectional"))
      (node (ref "RYS60") (pin "P$1") (pinfunction "1_P$1") (pintype "passive"))
    )
    (net (code "288") (name "PA_01") (class "Default")
      (node (ref "J10") (pin "P$22") (pinfunction "P$22_P$22") (pintype "bidirectional"))
      (node (ref "RYS20") (pin "P$1") (pinfunction "1_P$1") (pintype "passive"))
    )
    (net (code "289") (name "PA_08") (class "Default")
      (node (ref "J10") (pin "P$25") (pinfunction "P$25_P$25") (pintype "bidirectional"))
      (node (ref "RYS64") (pin "P$1") (pinfunction "1_P$1") (pintype "passive"))
    )
    (net (code "290") (name "PA_09") (class "Default")
      (node (ref "J10") (pin "P$24") (pinfunction "P$24_P$24") (pintype "bidirectional"))
      (node (ref "RYS22") (pin "P$1") (pinfunction "1_P$1") (pintype "passive"))
    )
    (net (code "291") (name "PA_10") (class "Default")
      (node (ref "J10") (pin "P$23") (pinfunction "P$23_P$23") (pintype "bidirectional"))
      (node (ref "RYS62") (pin "P$1") (pinfunction "1_P$1") (pintype "passive"))
    )
    (net (code "292") (name "VDD") (class "Default")
      (node (ref "J1") (pin "3") (pinfunction "3_3") (pintype "passive"))
      (node (ref "J1") (pin "4") (pinfunction "4_4") (pintype "passive"))
      (node (ref "R1") (pin "P$1") (pinfunction "1_P$1") (pintype "passive"))
      (node (ref "R10") (pin "P$1") (pinfunction "1_P$1") (pintype "passive"))
      (node (ref "R11") (pin "P$1") (pinfunction "1_P$1") (pintype "passive"))
      (node (ref "R12") (pin "P$1") (pinfunction "1_P$1") (pintype "passive"))
      (node (ref "R13") (pin "P$2") (pinfunction "2_P$2") (pintype "passive"))
      (node (ref "R14") (pin "P$1") (pinfunction "1_P$1") (pintype "passive"))
      (node (ref "R15") (pin "P$1") (pinfunction "1_P$1") (pintype "passive"))
      (node (ref "R16") (pin "P$1") (pinfunction "1_P$1") (pintype "passive"))
      (node (ref "R17") (pin "P$1") (pinfunction "1_P$1") (pintype "passive"))
      (node (ref "R2") (pin "P$1") (pinfunction "1_P$1") (pintype "passive"))
      (node (ref "R23") (pin "P$2") (pinfunction "2_P$2") (pintype "passive"))
      (node (ref "R24") (pin "P$2") (pinfunction "2_P$2") (pintype "passive"))
      (node (ref "R25") (pin "P$2") (pinfunction "2_P$2") (pintype "passive"))
      (node (ref "R26") (pin "P$2") (pinfunction "2_P$2") (pintype "passive"))
      (node (ref "R27") (pin "P$2") (pinfunction "2_P$2") (pintype "passive"))
      (node (ref "R28") (pin "P$2") (pinfunction "2_P$2") (pintype "passive"))
      (node (ref "R29") (pin "P$2") (pinfunction "2_P$2") (pintype "passive"))
      (node (ref "R3") (pin "P$1") (pinfunction "1_P$1") (pintype "passive"))
      (node (ref "R30") (pin "P$2") (pinfunction "2_P$2") (pintype "passive"))
      (node (ref "R31") (pin "P$2") (pinfunction "2_P$2") (pintype "passive"))
      (node (ref "R32") (pin "P$2") (pinfunction "2_P$2") (pintype "passive"))
      (node (ref "R33") (pin "P$2") (pinfunction "2_P$2") (pintype "passive"))
      (node (ref "R35") (pin "P$2") (pinfunction "2_P$2") (pintype "passive"))
      (node (ref "R36") (pin "P$2") (pinfunction "2_P$2") (pintype "passive"))
      (node (ref "R37") (pin "P$2") (pinfunction "2_P$2") (pintype "passive"))
      (node (ref "R38") (pin "P$2") (pinfunction "2_P$2") (pintype "passive"))
      (node (ref "R39") (pin "P$2") (pinfunction "2_P$2") (pintype "passive"))
      (node (ref "R4") (pin "P$1") (pinfunction "1_P$1") (pintype "passive"))
      (node (ref "R40") (pin "P$2") (pinfunction "2_P$2") (pintype "passive"))
      (node (ref "R41") (pin "P$2") (pinfunction "2_P$2") (pintype "passive"))
      (node (ref "R43") (pin "P$2") (pinfunction "2_P$2") (pintype "passive"))
      (node (ref "R44") (pin "P$2") (pinfunction "2_P$2") (pintype "passive"))
      (node (ref "R45") (pin "P$2") (pinfunction "2_P$2") (pintype "passive"))
      (node (ref "R47") (pin "P$2") (pinfunction "2_P$2") (pintype "passive"))
      (node (ref "R48") (pin "P$2") (pinfunction "2_P$2") (pintype "passive"))
      (node (ref "R49") (pin "P$2") (pinfunction "2_P$2") (pintype "passive"))
      (node (ref "R5") (pin "P$1") (pinfunction "1_P$1") (pintype "passive"))
      (node (ref "R51") (pin "P$2") (pinfunction "2_P$2") (pintype "passive"))
      (node (ref "R52") (pin "P$2") (pinfunction "2_P$2") (pintype "passive"))
      (node (ref "R53") (pin "P$2") (pinfunction "2_P$2") (pintype "passive"))
      (node (ref "R55") (pin "P$2") (pinfunction "2_P$2") (pintype "passive"))
      (node (ref "R56") (pin "P$2") (pinfunction "2_P$2") (pintype "passive"))
      (node (ref "R57") (pin "P$2") (pinfunction "2_P$2") (pintype "passive"))
      (node (ref "R59") (pin "P$2") (pinfunction "2_P$2") (pintype "passive"))
      (node (ref "R6") (pin "P$1") (pinfunction "1_P$1") (pintype "passive"))
      (node (ref "R60") (pin "P$2") (pinfunction "2_P$2") (pintype "passive"))
      (node (ref "R61") (pin "P$2") (pinfunction "2_P$2") (pintype "passive"))
      (node (ref "R63") (pin "P$2") (pinfunction "2_P$2") (pintype "passive"))
      (node (ref "R64") (pin "P$2") (pinfunction "2_P$2") (pintype "passive"))
      (node (ref "R65") (pin "P$2") (pinfunction "2_P$2") (pintype "passive"))
      (node (ref "R67") (pin "P$2") (pinfunction "2_P$2") (pintype "passive"))
      (node (ref "R68") (pin "P$2") (pinfunction "2_P$2") (pintype "passive"))
      (node (ref "R69") (pin "P$2") (pinfunction "2_P$2") (pintype "passive"))
      (node (ref "R7") (pin "P$1") (pinfunction "1_P$1") (pintype "passive"))
      (node (ref "R71") (pin "P$2") (pinfunction "2_P$2") (pintype "passive"))
      (node (ref "R72") (pin "P$2") (pinfunction "2_P$2") (pintype "passive"))
      (node (ref "R73") (pin "P$2") (pinfunction "2_P$2") (pintype "passive"))
      (node (ref "R75") (pin "P$2") (pinfunction "2_P$2") (pintype "passive"))
      (node (ref "R76") (pin "P$2") (pinfunction "2_P$2") (pintype "passive"))
      (node (ref "R77") (pin "P$2") (pinfunction "2_P$2") (pintype "passive"))
      (node (ref "R79") (pin "P$2") (pinfunction "2_P$2") (pintype "passive"))
      (node (ref "R8") (pin "P$1") (pinfunction "1_P$1") (pintype "passive"))
      (node (ref "R80") (pin "P$2") (pinfunction "2_P$2") (pintype "passive"))
      (node (ref "R81") (pin "P$2") (pinfunction "2_P$2") (pintype "passive"))
      (node (ref "R83") (pin "P$2") (pinfunction "2_P$2") (pintype "passive"))
      (node (ref "R84") (pin "P$2") (pinfunction "2_P$2") (pintype "passive"))
      (node (ref "R85") (pin "P$2") (pinfunction "2_P$2") (pintype "passive"))
      (node (ref "R87") (pin "P$2") (pinfunction "2_P$2") (pintype "passive"))
      (node (ref "R88") (pin "P$2") (pinfunction "2_P$2") (pintype "passive"))
      (node (ref "R89") (pin "P$2") (pinfunction "2_P$2") (pintype "passive"))
      (node (ref "R9") (pin "P$1") (pinfunction "1_P$1") (pintype "passive"))
      (node (ref "R91") (pin "P$2") (pinfunction "2_P$2") (pintype "passive"))
      (node (ref "R92") (pin "P$2") (pinfunction "2_P$2") (pintype "passive"))
      (node (ref "R93") (pin "P$2") (pinfunction "2_P$2") (pintype "passive"))
      (node (ref "R95") (pin "P$2") (pinfunction "2_P$2") (pintype "passive"))
      (node (ref "R97") (pin "P$2") (pinfunction "2_P$2") (pintype "passive"))
      (node (ref "R99") (pin "P$2") (pinfunction "2_P$2") (pintype "passive"))
      (node (ref "SW1") (pin "1") (pinfunction "1_1") (pintype "passive"))
      (node (ref "SW1") (pin "2") (pinfunction "2_2") (pintype "passive"))
      (node (ref "SW2") (pin "1") (pinfunction "1_1") (pintype "passive"))
      (node (ref "SW2") (pin "2") (pinfunction "2_2") (pintype "passive"))
      (node (ref "SW3") (pin "1") (pinfunction "1_1") (pintype "passive"))
      (node (ref "SW3") (pin "2") (pinfunction "2_2") (pintype "passive"))
      (node (ref "SW4") (pin "1") (pinfunction "1_1") (pintype "passive"))
      (node (ref "SW4") (pin "2") (pinfunction "2_2") (pintype "passive"))
    )
    (net (code "293") (name "VDD5") (class "Default")
      (node (ref "J1") (pin "5") (pinfunction "5_5") (pintype "passive"))
      (node (ref "J1") (pin "6") (pinfunction "6_6") (pintype "passive"))
    )
    (net (code "294") (name "VDD12") (class "Default")
      (node (ref "J1") (pin "7") (pinfunction "7_7") (pintype "passive"))
      (node (ref "J1") (pin "8") (pinfunction "8_8") (pintype "passive"))
    )
  )
)
